# Mk3_v3_1415926535.net
KiCad netlist of a schematic drawn in EAGLE
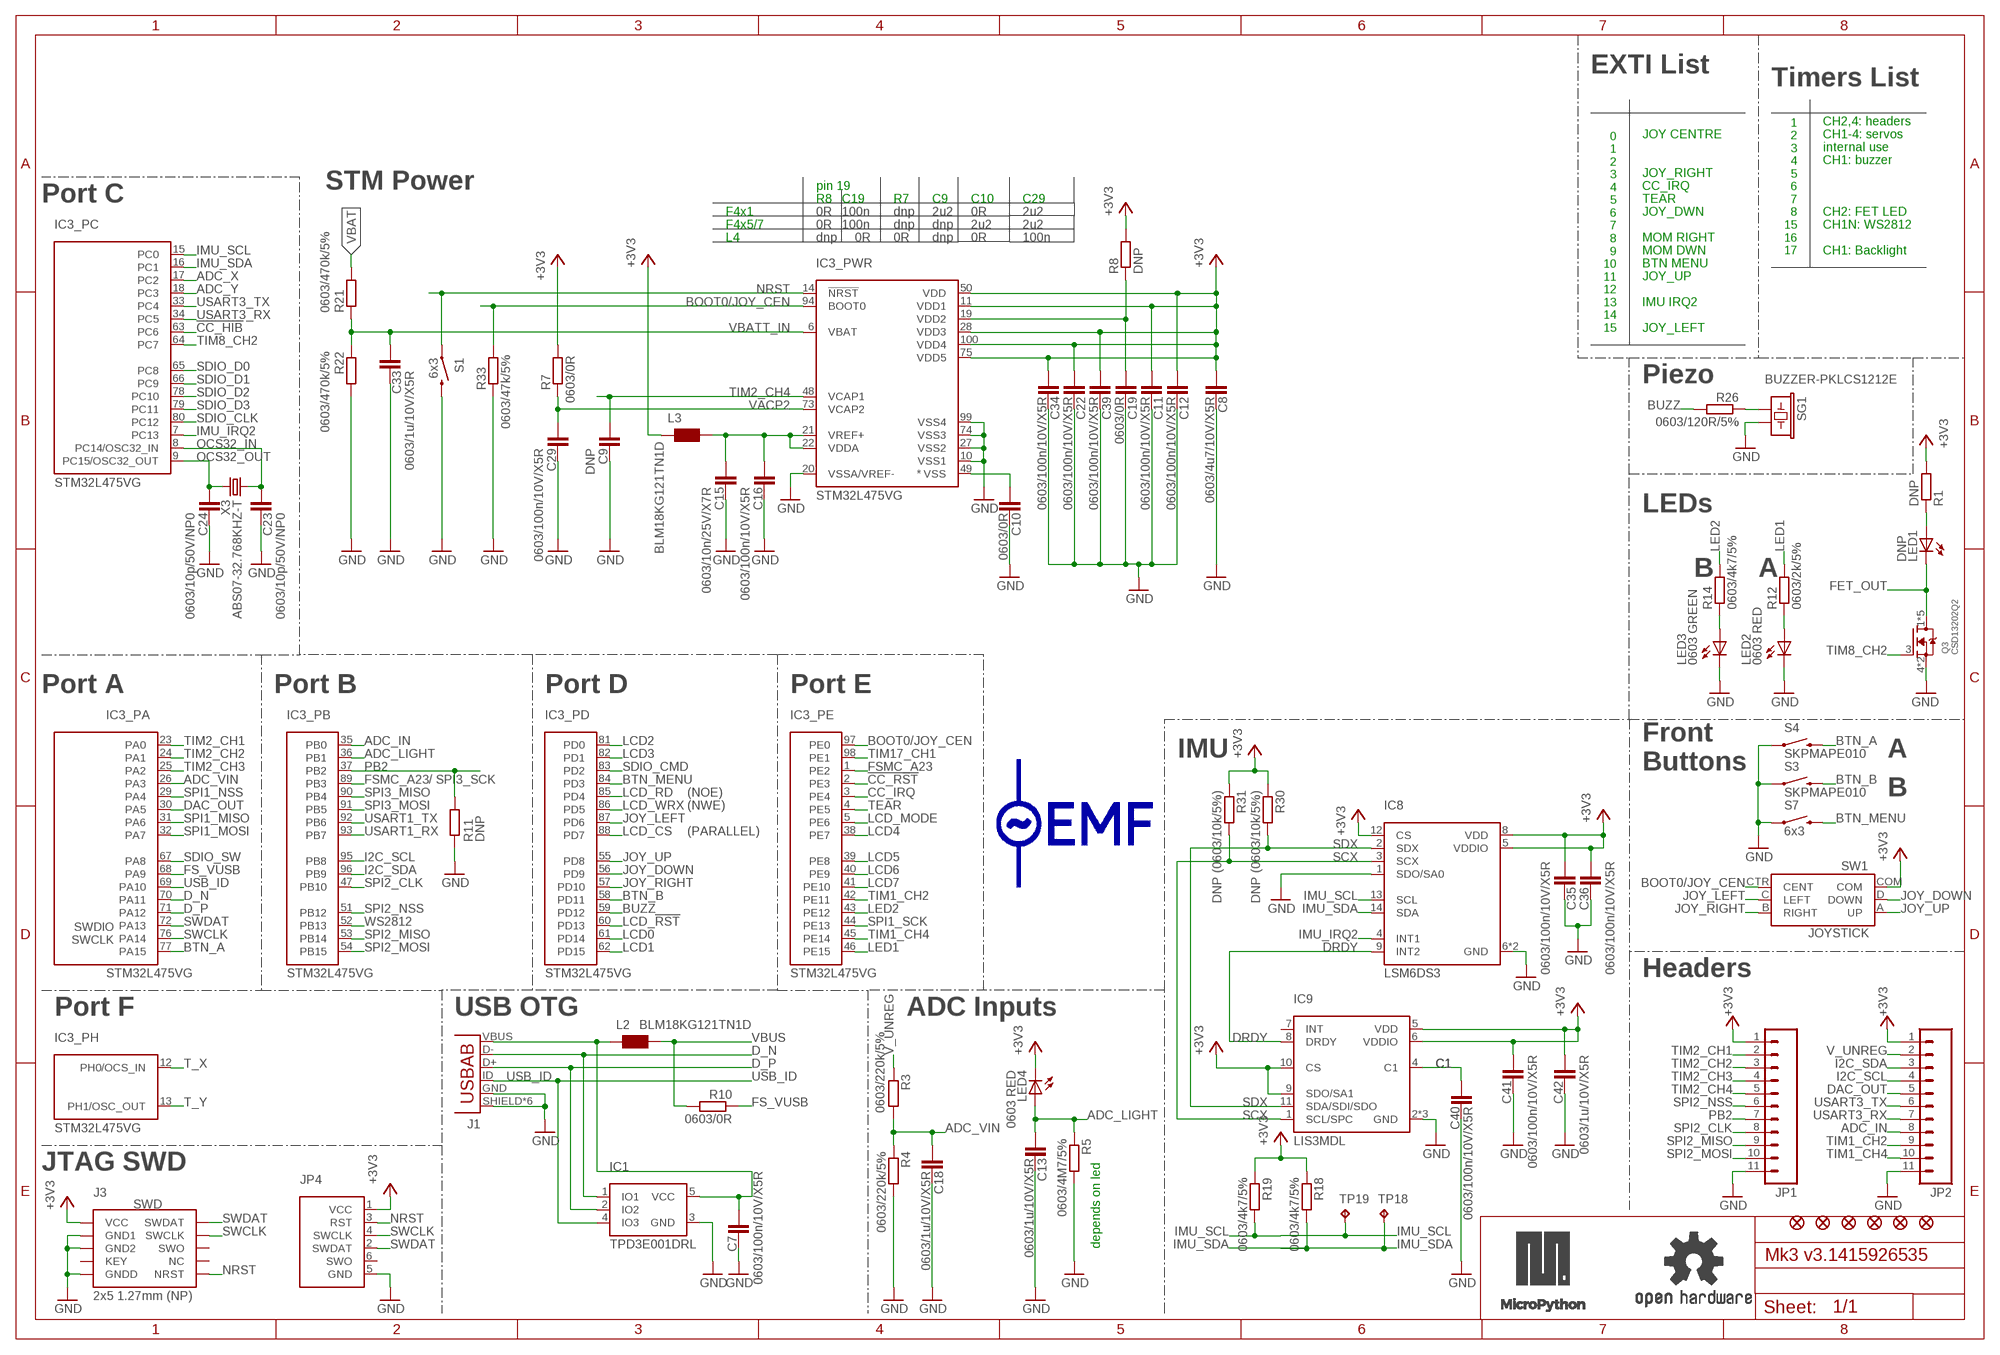
[diagram p0: schematic, sheet 1, part 1 of 2]
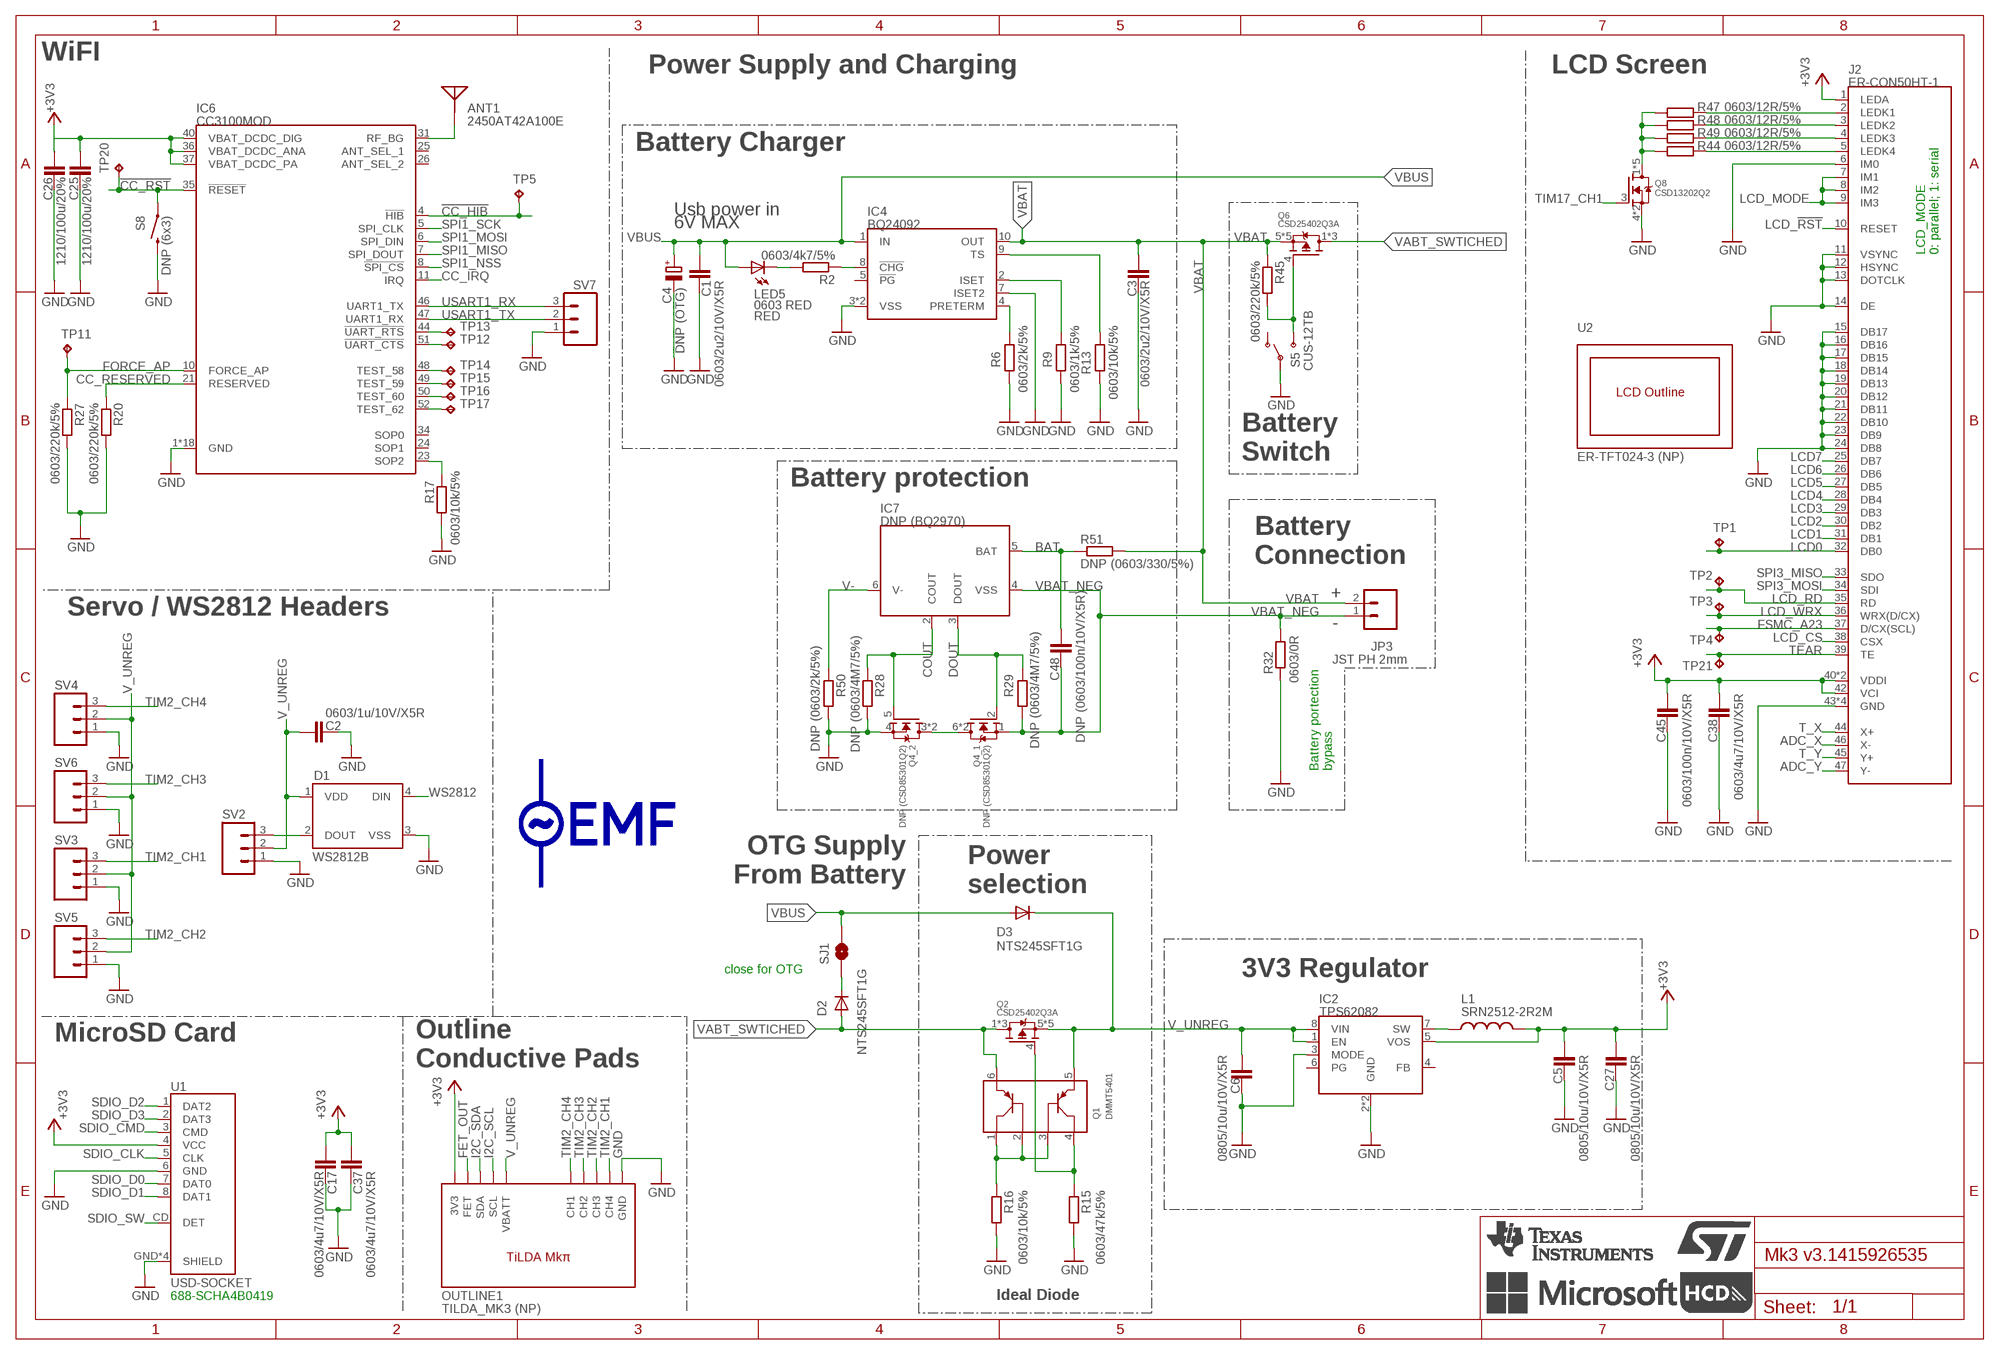
[diagram p1: schematic, sheet 1, part 2 of 2]

(export (version "E")
  (design (tool "Eeschema 10.0.6"))
  (components
    (comp (ref "ANT1")
      (value "2450AT42A100E")
      (footprint "eagle-import:2450AT42A100")
      (libsource (lib "eagle-import") (part "CHIPANT"))
    )
    (comp (ref "C1")
      (value "0603/2u2/10V/X5R")
      (footprint "eagle-import:C0603K-SMALL")
      (libsource (lib "eagle-import") (part "C-EUC0603K-SMALL"))
    )
    (comp (ref "C2")
      (value "0603/1u/10V/X5R")
      (footprint "eagle-import:C0603K-SMALL")
      (libsource (lib "eagle-import") (part "C-EUC0603K-SMALL"))
    )
    (comp (ref "C3")
      (value "0603/2u2/10V/X5R")
      (footprint "eagle-import:C0603K-SMALL")
      (libsource (lib "eagle-import") (part "C-EUC0603K-SMALL"))
    )
    (comp (ref "C4")
      (value "DNP (OTG)")
      (footprint "eagle-import:E2,5-6")
      (libsource (lib "eagle-import") (part "CPOL-EUE2.5-6"))
    )
    (comp (ref "C5")
      (value "0805/10u/10V/X5R")
      (footprint "eagle-import:C0805-N")
      (libsource (lib "eagle-import") (part "C-EUC0805-N"))
    )
    (comp (ref "C6")
      (value "0805/10u/10V/X5R")
      (footprint "eagle-import:C0805-N")
      (libsource (lib "eagle-import") (part "C-EUC0805-N"))
    )
    (comp (ref "C7")
      (value "0603/100n/10V/X5R")
      (footprint "eagle-import:C0603K-SMALL")
      (libsource (lib "eagle-import") (part "C-EUC0603K-SMALL"))
    )
    (comp (ref "C8")
      (value "0603/4u7/10V/X5R")
      (footprint "eagle-import:C0603K-SMALL")
      (libsource (lib "eagle-import") (part "C-EUC0603K-SMALL"))
    )
    (comp (ref "C9")
      (value "DNP")
      (footprint "eagle-import:C0603K-SMALL")
      (libsource (lib "eagle-import") (part "C-EUC0603K-SMALL"))
    )
    (comp (ref "C10")
      (value "0603/0R")
      (footprint "eagle-import:C0603K-SMALL")
      (libsource (lib "eagle-import") (part "C-EUC0603K-SMALL"))
    )
    (comp (ref "C11")
      (value "0603/100n/10V/X5R")
      (footprint "eagle-import:C0603K-SMALL")
      (libsource (lib "eagle-import") (part "C-EUC0603K-SMALL"))
    )
    (comp (ref "C12")
      (value "0603/100n/10V/X5R")
      (footprint "eagle-import:C0603K-SMALL")
      (libsource (lib "eagle-import") (part "C-EUC0603K-SMALL"))
    )
    (comp (ref "C13")
      (value "0603/1u/10V/X5R")
      (footprint "eagle-import:C0603K-SMALL")
      (libsource (lib "eagle-import") (part "C-EUC0603K-SMALL"))
    )
    (comp (ref "C15")
      (value "0603/10n/25V/X7R")
      (footprint "eagle-import:C0603K-SMALL")
      (libsource (lib "eagle-import") (part "C-EUC0603K-SMALL"))
    )
    (comp (ref "C16")
      (value "0603/100n/10V/X5R")
      (footprint "eagle-import:C0603K-SMALL")
      (libsource (lib "eagle-import") (part "C-EUC0603K-SMALL"))
    )
    (comp (ref "C17")
      (value "0603/4u7/10V/X5R")
      (footprint "eagle-import:C0603K-SMALL")
      (libsource (lib "eagle-import") (part "C-EUC0603K-SMALL"))
    )
    (comp (ref "C18")
      (value "0603/1u/10V/X5R")
      (footprint "eagle-import:C0603K-SMALL")
      (libsource (lib "eagle-import") (part "C-EUC0603K-SMALL"))
    )
    (comp (ref "C19")
      (value "0603/0R")
      (footprint "eagle-import:C0603K-SMALL")
      (libsource (lib "eagle-import") (part "C-EUC0603K-SMALL"))
    )
    (comp (ref "C22")
      (value "0603/100n/10V/X5R")
      (footprint "eagle-import:C0603K-SMALL")
      (libsource (lib "eagle-import") (part "C-EUC0603K-SMALL"))
    )
    (comp (ref "C23")
      (value "0603/10p/50V/NP0")
      (footprint "eagle-import:C0603K-SMALL")
      (libsource (lib "eagle-import") (part "C-EUC0603K-SMALL"))
    )
    (comp (ref "C24")
      (value "0603/10p/50V/NP0")
      (footprint "eagle-import:C0603K-SMALL")
      (libsource (lib "eagle-import") (part "C-EUC0603K-SMALL"))
    )
    (comp (ref "C25")
      (value "1210/100u/20%")
      (footprint "eagle-import:C1210K")
      (libsource (lib "eagle-import") (part "C-EUC1210K"))
    )
    (comp (ref "C26")
      (value "1210/100u/20%")
      (footprint "eagle-import:C1210K")
      (libsource (lib "eagle-import") (part "C-EUC1210K"))
    )
    (comp (ref "C27")
      (value "0805/10u/10V/X5R")
      (footprint "eagle-import:C0805-N")
      (libsource (lib "eagle-import") (part "C-EUC0805-N"))
    )
    (comp (ref "C29")
      (value "0603/100n/10V/X5R")
      (footprint "eagle-import:C0603K-SMALL")
      (libsource (lib "eagle-import") (part "C-EUC0603K-SMALL"))
    )
    (comp (ref "C33")
      (value "0603/1u/10V/X5R")
      (footprint "eagle-import:C0603K-SMALL")
      (libsource (lib "eagle-import") (part "C-EUC0603K-SMALL"))
    )
    (comp (ref "C34")
      (value "0603/100n/10V/X5R")
      (footprint "eagle-import:C0603K-SMALL")
      (libsource (lib "eagle-import") (part "C-EUC0603K-SMALL"))
    )
    (comp (ref "C35")
      (value "0603/100n/10V/X5R")
      (footprint "eagle-import:C0603K-SMALL")
      (libsource (lib "eagle-import") (part "C-EUC0603K-SMALL"))
    )
    (comp (ref "C36")
      (value "0603/100n/10V/X5R")
      (footprint "eagle-import:C0603K-SMALL")
      (libsource (lib "eagle-import") (part "C-EUC0603K-SMALL"))
    )
    (comp (ref "C37")
      (value "0603/4u7/10V/X5R")
      (footprint "eagle-import:C0603K-SMALL")
      (libsource (lib "eagle-import") (part "C-EUC0603K-SMALL"))
    )
    (comp (ref "C38")
      (value "0603/4u7/10V/X5R")
      (footprint "eagle-import:C0603K-SMALL")
      (libsource (lib "eagle-import") (part "C-EUC0603K-SMALL"))
    )
    (comp (ref "C39")
      (value "0603/100n/10V/X5R")
      (footprint "eagle-import:C0603K-SMALL")
      (libsource (lib "eagle-import") (part "C-EUC0603K-SMALL"))
    )
    (comp (ref "C40")
      (value "0603/100n/10V/X5R")
      (footprint "eagle-import:C0603K-SMALL")
      (libsource (lib "eagle-import") (part "C-EUC0603K-SMALL"))
    )
    (comp (ref "C41")
      (value "0603/100n/10V/X5R")
      (footprint "eagle-import:C0603K-SMALL")
      (libsource (lib "eagle-import") (part "C-EUC0603K-SMALL"))
    )
    (comp (ref "C42")
      (value "0603/1u/10V/X5R")
      (footprint "eagle-import:C0603K-SMALL")
      (libsource (lib "eagle-import") (part "C-EUC0603K-SMALL"))
    )
    (comp (ref "C45")
      (value "0603/100n/10V/X5R")
      (footprint "eagle-import:C0603K-SMALL")
      (libsource (lib "eagle-import") (part "C-EUC0603K-SMALL"))
    )
    (comp (ref "C48")
      (value "DNP (0603/100n/10V/X5R)")
      (footprint "eagle-import:C0603K-SMALL")
      (libsource (lib "eagle-import") (part "C-EUC0603K-SMALL"))
    )
    (comp (ref "D1")
      (value "WS2812B")
      (footprint "eagle-import:WS2812B")
      (libsource (lib "eagle-import") (part "WS2812B"))
    )
    (comp (ref "D2")
      (value "NTS245SFT1G")
      (footprint "eagle-import:SOD123")
      (libsource (lib "eagle-import") (part "1N4148-SOD123"))
    )
    (comp (ref "D3")
      (value "NTS245SFT1G")
      (footprint "eagle-import:SOD123")
      (libsource (lib "eagle-import") (part "1N4148-SOD123"))
    )
    (comp (ref "FID1")
      (value "FIDUCIAL1X2.5-STOP")
      (footprint "eagle-import:FIDUCIAL-1X2.5-STOP")
      (libsource (lib "eagle-import") (part "FIDUCIAL1X2.5-STOP"))
    )
    (comp (ref "FID2")
      (value "FIDUCIAL1X2.5-STOP")
      (footprint "eagle-import:FIDUCIAL-1X2.5-STOP")
      (libsource (lib "eagle-import") (part "FIDUCIAL1X2.5-STOP"))
    )
    (comp (ref "FID3")
      (value "FIDUCIAL1X2.5-STOP")
      (footprint "eagle-import:FIDUCIAL-1X2.5-STOP")
      (libsource (lib "eagle-import") (part "FIDUCIAL1X2.5-STOP"))
    )
    (comp (ref "FID4")
      (value "FIDUCIAL1X2.5-STOP")
      (footprint "eagle-import:FIDUCIAL-1X2.5-STOP")
      (libsource (lib "eagle-import") (part "FIDUCIAL1X2.5-STOP"))
    )
    (comp (ref "FID5")
      (value "FIDUCIAL1X2.5-STOP")
      (footprint "eagle-import:FIDUCIAL-1X2.5-STOP")
      (libsource (lib "eagle-import") (part "FIDUCIAL1X2.5-STOP"))
    )
    (comp (ref "FID6")
      (value "FIDUCIAL1X2.5-STOP")
      (footprint "eagle-import:FIDUCIAL-1X2.5-STOP")
      (libsource (lib "eagle-import") (part "FIDUCIAL1X2.5-STOP"))
    )
    (comp (ref "IC1")
      (value "TPD3E001DRL")
      (footprint "eagle-import:DRL-5")
      (libsource (lib "eagle-import") (part "TPD3E001DRL"))
    )
    (comp (ref "IC2")
      (value "TPS62082")
      (footprint "eagle-import:WSON8")
      (libsource (lib "eagle-import") (part "TPS62082"))
    )
    (comp (ref "IC3")
      (value "STM32L475VG")
      (footprint "eagle-import:TQFP100")
      (fields (field (name "FARNELL") "2432116"))
      (libsource (lib "eagle-import") (part "STM32F401V"))
    )
    (comp (ref "IC4")
      (value "BQ24092")
      (footprint "eagle-import:HVSSOP10")
      (libsource (lib "eagle-import") (part "BQ2409X"))
    )
    (comp (ref "IC6")
      (value "CC3100MOD")
      (footprint "eagle-import:CC3100MOD-LWK")
      (libsource (lib "eagle-import") (part "CC3100MOD-LWK"))
    )
    (comp (ref "IC7")
      (value "DNP (BQ2970)")
      (footprint "eagle-import:WSON-6")
      (libsource (lib "eagle-import") (part "BQ2970"))
    )
    (comp (ref "IC8")
      (value "LSM6DS3")
      (footprint "eagle-import:LGA14")
      (libsource (lib "eagle-import") (part "LSM6DS3"))
    )
    (comp (ref "IC9")
      (value "LIS3MDL")
      (footprint "eagle-import:LGA12")
      (libsource (lib "eagle-import") (part "LIS3MDL"))
    )
    (comp (ref "J1")
      (value "ZX62-AB-5PA(11)")
      (footprint "eagle-import:USB-AB-MICRO-SMD_LWK")
      (libsource (lib "eagle-import") (part "USB-AB-LWK"))
    )
    (comp (ref "J2")
      (value "ER-CON50HT-1")
      (footprint "eagle-import:FH12-50S-0.5SH")
      (libsource (lib "eagle-import") (part "ER-TFT024-3"))
    )
    (comp (ref "J3")
      (value "2x5 1.27mm (NP)")
      (footprint "eagle-import:PINHEAD_2X05_127")
      (libsource (lib "eagle-import") (part "SWD_SHROUD-PINHEAD"))
    )
    (comp (ref "JP1")
      (value "(NP)")
      (footprint "eagle-import:1X11")
      (libsource (lib "eagle-import") (part "M11PTH"))
    )
    (comp (ref "JP2")
      (value "(NP)")
      (footprint "eagle-import:1X11")
      (libsource (lib "eagle-import") (part "M11PTH"))
    )
    (comp (ref "JP3")
      (value "JST PH 2mm")
      (footprint "eagle-import:JST-2-SMD")
      (libsource (lib "eagle-import") (part "M02-JST-2MM-SMT"))
    )
    (comp (ref "JP4")
      (value "(NP)")
      (footprint "eagle-import:TC2030-MCP-NL")
      (libsource (lib "eagle-import") (part "TC2030-SWDNL"))
    )
    (comp (ref "L1")
      (value "SRN2512-2R2M")
      (footprint "eagle-import:1008")
      (libsource (lib "eagle-import") (part "INDUCTOR1008"))
    )
    (comp (ref "L2")
      (value "BLM18KG121TN1D")
      (footprint "eagle-import:WUERTH-0805")
      (libsource (lib "eagle-import") (part "WE-CBF_0805"))
    )
    (comp (ref "L3")
      (value "BLM18KG121TN1D")
      (footprint "eagle-import:WUERTH-0805")
      (libsource (lib "eagle-import") (part "WE-CBF_0805"))
    )
    (comp (ref "LED1")
      (value "DNP")
      (footprint "eagle-import:LED5MM")
      (libsource (lib "eagle-import") (part "LED5MM"))
    )
    (comp (ref "LED2")
      (value "0603 RED")
      (footprint "eagle-import:LED-0603-CORRECT")
      (fields (field (name "COLOUR") "RED"))
      (libsource (lib "eagle-import") (part "LED0603-CORRECT"))
    )
    (comp (ref "LED3")
      (value "0603 GREEN")
      (footprint "eagle-import:LED-0603-CORRECT")
      (fields (field (name "COLOUR") "GREEN"))
      (libsource (lib "eagle-import") (part "LED0603-CORRECT"))
    )
    (comp (ref "LED4")
      (value "0603 RED")
      (footprint "eagle-import:LED-0603-CORRECT")
      (libsource (lib "eagle-import") (part "LED0603-CORRECT"))
    )
    (comp (ref "LED5")
      (value "0603 RED")
      (footprint "eagle-import:LED-0603-CORRECT")
      (fields (field (name "COLOUR") "RED"))
      (libsource (lib "eagle-import") (part "LED0603-CORRECT"))
    )
    (comp (ref "LOGO1")
      (value "OSHW-LOGOM (NP)")
      (footprint "eagle-import:OSHW-LOGO-M")
      (libsource (lib "eagle-import") (part "OSHW-LOGOM"))
    )
    (comp (ref "LOGO2")
      (value "LOGO_TI-4MM (NP)")
      (footprint "eagle-import:LOGO_TI_4MM")
      (libsource (lib "eagle-import") (part "LOGO_TI-4MM"))
    )
    (comp (ref "LOGO3")
      (value "LOGO_ST-4MM (NP)")
      (footprint "eagle-import:LOGO_ST_4MM")
      (libsource (lib "eagle-import") (part "LOGO_ST-4MM"))
    )
    (comp (ref "LOGO4")
      (value "LOGO_HCD-4MM (NP)")
      (footprint "eagle-import:LOGO_HDC_4MM")
      (libsource (lib "eagle-import") (part "LOGO_HCD-4MM"))
    )
    (comp (ref "LOGO5")
      (value "LOGO_MICROSOFT-4MM (NP)")
      (footprint "eagle-import:LOGO_MS_4MM")
      (libsource (lib "eagle-import") (part "LOGO_MICROSOFT-4MM"))
    )
    (comp (ref "LOGO6")
      (value "LOGO_MICROPYTHON-8MM (NP)")
      (footprint "eagle-import:LOGO_MICROPYTHON_8MM")
      (libsource (lib "eagle-import") (part "LOGO_MICROPYTHON-8MM"))
    )
    (comp (ref "OUTLINE1")
      (value "TILDA_MK3 (NP)")
      (footprint "eagle-import:TILDA_MKE_OUTLINE")
      (libsource (lib "eagle-import") (part "TILDA_MK3_BOARDOUTLINE"))
    )
    (comp (ref "Q1")
      (value "DMMT5401")
      (footprint "eagle-import:SOT26")
      (libsource (lib "eagle-import") (part "DMMT5401"))
    )
    (comp (ref "Q2")
      (value "CSD25402Q3A")
      (footprint "eagle-import:Q3A")
      (libsource (lib "eagle-import") (part "CSD25402Q3A"))
    )
    (comp (ref "Q3")
      (value "CSD13202Q2")
      (footprint "eagle-import:Q2")
      (libsource (lib "eagle-import") (part "CSD13202Q2"))
    )
    (comp (ref "Q4")
      (value "DNP (CSD85301Q2)")
      (footprint "eagle-import:Q2_DUAL")
      (fields (field (name "FARNELL") "2470183"))
      (libsource (lib "eagle-import") (part "CSD85301Q2"))
    )
    (comp (ref "Q6")
      (value "CSD25402Q3A")
      (footprint "eagle-import:Q3A")
      (libsource (lib "eagle-import") (part "CSD25402Q3A"))
    )
    (comp (ref "Q8")
      (value "CSD13202Q2")
      (footprint "eagle-import:Q2")
      (libsource (lib "eagle-import") (part "CSD13202Q2"))
    )
    (comp (ref "R1")
      (value "DNP")
      (footprint "eagle-import:0207_10")
      (libsource (lib "eagle-import") (part "R-EU_0207/10"))
    )
    (comp (ref "R2")
      (value "0603/4k7/5%")
      (footprint "eagle-import:C0603K-SMALL")
      (libsource (lib "eagle-import") (part "R-EU_0603K-SMALL"))
    )
    (comp (ref "R3")
      (value "0603/220k/5%")
      (footprint "eagle-import:C0603K-SMALL")
      (libsource (lib "eagle-import") (part "R-EU_0603K-SMALL"))
    )
    (comp (ref "R4")
      (value "0603/220k/5%")
      (footprint "eagle-import:C0603K-SMALL")
      (libsource (lib "eagle-import") (part "R-EU_0603K-SMALL"))
    )
    (comp (ref "R5")
      (value "0603/4M7/5%")
      (footprint "eagle-import:C0603K-SMALL")
      (libsource (lib "eagle-import") (part "R-EU_0603K-SMALL"))
    )
    (comp (ref "R6")
      (value "0603/2k/5%")
      (footprint "eagle-import:C0603K-SMALL")
      (libsource (lib "eagle-import") (part "R-EU_0603K-SMALL"))
    )
    (comp (ref "R7")
      (value "0603/0R")
      (footprint "eagle-import:C0603K-SMALL")
      (libsource (lib "eagle-import") (part "R-EU_0603K-SMALL"))
    )
    (comp (ref "R8")
      (value "DNP")
      (footprint "eagle-import:C0603K-SMALL")
      (libsource (lib "eagle-import") (part "R-EU_0603K-SMALL"))
    )
    (comp (ref "R9")
      (value "0603/1k/5%")
      (footprint "eagle-import:C0603K-SMALL")
      (libsource (lib "eagle-import") (part "R-EU_0603K-SMALL"))
    )
    (comp (ref "R10")
      (value "0603/0R")
      (footprint "eagle-import:C0603K-SMALL")
      (libsource (lib "eagle-import") (part "R-EU_0603K-SMALL"))
    )
    (comp (ref "R11")
      (value "DNP")
      (footprint "eagle-import:C0603K-SMALL")
      (libsource (lib "eagle-import") (part "R-EU_0603K-SMALL"))
    )
    (comp (ref "R12")
      (value "0603/2k/5%")
      (footprint "eagle-import:C0603K-SMALL")
      (libsource (lib "eagle-import") (part "R-EU_0603K-SMALL"))
    )
    (comp (ref "R13")
      (value "0603/10k/5%")
      (footprint "eagle-import:C0603K-SMALL")
      (libsource (lib "eagle-import") (part "R-EU_0603K-SMALL"))
    )
    (comp (ref "R14")
      (value "0603/4k7/5%")
      (footprint "eagle-import:C0603K-SMALL")
      (libsource (lib "eagle-import") (part "R-EU_0603K-SMALL"))
    )
    (comp (ref "R15")
      (value "0603/47k/5%")
      (footprint "eagle-import:C0603K-SMALL")
      (libsource (lib "eagle-import") (part "R-EU_0603K-SMALL"))
    )
    (comp (ref "R16")
      (value "0603/10k/5%")
      (footprint "eagle-import:C0603K-SMALL")
      (libsource (lib "eagle-import") (part "R-EU_0603K-SMALL"))
    )
    (comp (ref "R17")
      (value "0603/10k/5%")
      (footprint "eagle-import:C0603K-SMALL")
      (libsource (lib "eagle-import") (part "R-EU_0603K-SMALL"))
    )
    (comp (ref "R18")
      (value "0603/4k7/5%")
      (footprint "eagle-import:C0603K-SMALL")
      (libsource (lib "eagle-import") (part "R-EU_0603K-SMALL"))
    )
    (comp (ref "R19")
      (value "0603/4k7/5%")
      (footprint "eagle-import:C0603K-SMALL")
      (libsource (lib "eagle-import") (part "R-EU_0603K-SMALL"))
    )
    (comp (ref "R20")
      (value "0603/220k/5%")
      (footprint "eagle-import:C0603K-SMALL")
      (libsource (lib "eagle-import") (part "R-EU_0603K-SMALL"))
    )
    (comp (ref "R21")
      (value "0603/470k/5%")
      (footprint "eagle-import:C0603K-SMALL")
      (libsource (lib "eagle-import") (part "R-EU_0603K-SMALL"))
    )
    (comp (ref "R22")
      (value "0603/470k/5%")
      (footprint "eagle-import:C0603K-SMALL")
      (libsource (lib "eagle-import") (part "R-EU_0603K-SMALL"))
    )
    (comp (ref "R26")
      (value "0603/120R/5%")
      (footprint "eagle-import:C0603K-SMALL")
      (libsource (lib "eagle-import") (part "R-EU_0603K-SMALL"))
    )
    (comp (ref "R27")
      (value "0603/220k/5%")
      (footprint "eagle-import:C0603K-SMALL")
      (libsource (lib "eagle-import") (part "R-EU_0603K-SMALL"))
    )
    (comp (ref "R28")
      (value "DNP (0603/4M7/5%)")
      (footprint "eagle-import:C0603K-SMALL")
      (libsource (lib "eagle-import") (part "R-EU_0603K-SMALL"))
    )
    (comp (ref "R29")
      (value "DNP (0603/4M7/5%)")
      (footprint "eagle-import:C0603K-SMALL")
      (libsource (lib "eagle-import") (part "R-EU_0603K-SMALL"))
    )
    (comp (ref "R30")
      (value "DNP (0603/10k/5%)")
      (footprint "eagle-import:C0603K-SMALL")
      (libsource (lib "eagle-import") (part "R-EU_0603K-SMALL"))
    )
    (comp (ref "R31")
      (value "DNP (0603/10k/5%)")
      (footprint "eagle-import:C0603K-SMALL")
      (libsource (lib "eagle-import") (part "R-EU_0603K-SMALL"))
    )
    (comp (ref "R32")
      (value "0603/0R")
      (footprint "eagle-import:C0603K-SMALL")
      (libsource (lib "eagle-import") (part "R-EU_0603K-SMALL"))
    )
    (comp (ref "R33")
      (value "0603/47k/5%")
      (footprint "eagle-import:C0603K-SMALL")
      (libsource (lib "eagle-import") (part "R-EU_0603K-SMALL"))
    )
    (comp (ref "R44")
      (value "0603/12R/5%")
      (footprint "eagle-import:C0603K-SMALL")
      (libsource (lib "eagle-import") (part "R-EU_0603K-SMALL"))
    )
    (comp (ref "R45")
      (value "0603/220k/5%")
      (footprint "eagle-import:C0603K-SMALL")
      (libsource (lib "eagle-import") (part "R-EU_0603K-SMALL"))
    )
    (comp (ref "R47")
      (value "0603/12R/5%")
      (footprint "eagle-import:C0603K-SMALL")
      (libsource (lib "eagle-import") (part "R-EU_0603K-SMALL"))
    )
    (comp (ref "R48")
      (value "0603/12R/5%")
      (footprint "eagle-import:C0603K-SMALL")
      (libsource (lib "eagle-import") (part "R-EU_0603K-SMALL"))
    )
    (comp (ref "R49")
      (value "0603/12R/5%")
      (footprint "eagle-import:C0603K-SMALL")
      (libsource (lib "eagle-import") (part "R-EU_0603K-SMALL"))
    )
    (comp (ref "R50")
      (value "DNP (0603/2k/5%)")
      (footprint "eagle-import:C0603K-SMALL")
      (libsource (lib "eagle-import") (part "R-EU_0603K-SMALL"))
    )
    (comp (ref "R51")
      (value "DNP (0603/330/5%)")
      (footprint "eagle-import:C0603K-SMALL")
      (libsource (lib "eagle-import") (part "R-EU_0603K-SMALL"))
    )
    (comp (ref "S1")
      (value "6x3")
      (footprint "eagle-import:TACTILE-SWITCH-1101NE")
      (libsource (lib "eagle-import") (part "SWITCH-MOMENTARY-2-SMD-1101NE"))
    )
    (comp (ref "S3")
      (value "SKPMAPE010")
      (footprint "eagle-import:SKPMAPE010-COMBINED")
      (libsource (lib "eagle-import") (part "SWITCH-MOMENTARY-2-SKPMAPE010-COMBINED"))
    )
    (comp (ref "S4")
      (value "SKPMAPE010")
      (footprint "eagle-import:SKPMAPE010-COMBINED")
      (libsource (lib "eagle-import") (part "SWITCH-MOMENTARY-2-SKPMAPE010-COMBINED"))
    )
    (comp (ref "S5")
      (value "CUS-12TB")
      (footprint "eagle-import:SWITCH-SPST-SMD-A")
      (libsource (lib "eagle-import") (part "SWITCH-SPST-SMD-A"))
    )
    (comp (ref "S7")
      (value "6x3")
      (footprint "eagle-import:TACTILE-SWITCH-1101NE")
      (libsource (lib "eagle-import") (part "SWITCH-MOMENTARY-2-SMD-1101NE"))
    )
    (comp (ref "S8")
      (value "DNP (6x3)")
      (footprint "eagle-import:TACTILE-SWITCH-1101NE")
      (libsource (lib "eagle-import") (part "SWITCH-MOMENTARY-2-SMD-1101NE"))
    )
    (comp (ref "SG1")
      (value "BUZZER-PKLCS1212E")
      (footprint "eagle-import:BUZZER-PKLCS1212E")
      (libsource (lib "eagle-import") (part "BUZZER-PKLCS1212E"))
    )
    (comp (ref "SJ1")
      (value "OTG (NP)")
      (footprint "eagle-import:SJ_2S-NO")
      (libsource (lib "eagle-import") (part "SOLDERJUMPERNO"))
    )
    (comp (ref "SV2")
      (value "(NP)")
      (footprint "eagle-import:1X03")
      (libsource (lib "eagle-import") (part "M03PTH"))
    )
    (comp (ref "SV3")
      (value "(NP)")
      (footprint "eagle-import:1X03")
      (libsource (lib "eagle-import") (part "M03PTH"))
    )
    (comp (ref "SV4")
      (value "(NP)")
      (footprint "eagle-import:1X03")
      (libsource (lib "eagle-import") (part "M03PTH"))
    )
    (comp (ref "SV5")
      (value "(NP)")
      (footprint "eagle-import:1X03")
      (libsource (lib "eagle-import") (part "M03PTH"))
    )
    (comp (ref "SV6")
      (value "(NP)")
      (footprint "eagle-import:1X03")
      (libsource (lib "eagle-import") (part "M03PTH"))
    )
    (comp (ref "SV7")
      (value "(NP)")
      (footprint "eagle-import:1X03")
      (libsource (lib "eagle-import") (part "M03PTH"))
    )
    (comp (ref "SW1")
      (value "JOYSTICK")
      (footprint "eagle-import:JOYSTICK_MULTICOMP_NOSILK")
      (libsource (lib "eagle-import") (part "JOYSTICK_MINI_MULTICOM_NOSILK"))
    )
    (comp (ref "TP1")
      (value "(NP)")
      (footprint "eagle-import:B1,27")
      (libsource (lib "eagle-import") (part "TPB1,27"))
    )
    (comp (ref "TP2")
      (value "(NP)")
      (footprint "eagle-import:B1,27")
      (libsource (lib "eagle-import") (part "TPB1,27"))
    )
    (comp (ref "TP3")
      (value "(NP)")
      (footprint "eagle-import:B1,27")
      (libsource (lib "eagle-import") (part "TPB1,27"))
    )
    (comp (ref "TP4")
      (value "(NP)")
      (footprint "eagle-import:B1,27")
      (libsource (lib "eagle-import") (part "TPB1,27"))
    )
    (comp (ref "TP5")
      (value "(NP)")
      (footprint "eagle-import:B1,27")
      (libsource (lib "eagle-import") (part "TPB1,27"))
    )
    (comp (ref "TP11")
      (value "(NP)")
      (footprint "eagle-import:B1,27")
      (libsource (lib "eagle-import") (part "TPB1,27"))
    )
    (comp (ref "TP12")
      (value "(NP)")
      (footprint "eagle-import:B1,27")
      (libsource (lib "eagle-import") (part "TPB1,27"))
    )
    (comp (ref "TP13")
      (value "(NP)")
      (footprint "eagle-import:B1,27")
      (libsource (lib "eagle-import") (part "TPB1,27"))
    )
    (comp (ref "TP14")
      (value "(NP)")
      (footprint "eagle-import:B1,27")
      (libsource (lib "eagle-import") (part "TPB1,27"))
    )
    (comp (ref "TP15")
      (value "(NP)")
      (footprint "eagle-import:B1,27")
      (libsource (lib "eagle-import") (part "TPB1,27"))
    )
    (comp (ref "TP16")
      (value "(NP)")
      (footprint "eagle-import:B1,27")
      (libsource (lib "eagle-import") (part "TPB1,27"))
    )
    (comp (ref "TP17")
      (value "(NP)")
      (footprint "eagle-import:B1,27")
      (libsource (lib "eagle-import") (part "TPB1,27"))
    )
    (comp (ref "TP18")
      (value "(NP)")
      (footprint "eagle-import:B1,27")
      (libsource (lib "eagle-import") (part "TPB1,27"))
    )
    (comp (ref "TP19")
      (value "(NP)")
      (footprint "eagle-import:B1,27")
      (libsource (lib "eagle-import") (part "TPB1,27"))
    )
    (comp (ref "TP20")
      (value "(NP)")
      (footprint "eagle-import:B1,27")
      (libsource (lib "eagle-import") (part "TPB1,27"))
    )
    (comp (ref "TP21")
      (value "(NP)")
      (footprint "eagle-import:B1,27")
      (libsource (lib "eagle-import") (part "TPB1,27"))
    )
    (comp (ref "U1")
      (value "USD-SOCKET")
      (footprint "eagle-import:0011XAAX09X")
      (libsource (lib "eagle-import") (part "USD-SOCKET-SDIO"))
    )
    (comp (ref "U2")
      (value "ER-TFT024-3 (NP)")
      (footprint "eagle-import:ER-TFT024-3")
      (libsource (lib "eagle-import") (part "ER-TFT024-3-OUTLINE"))
    )
    (comp (ref "X3")
      (value "ABS07-32.768KHZ-T")
      (footprint "eagle-import:RESONATOR_EPSON_FC_145")
      (libsource (lib "eagle-import") (part "RESONATOR_EPSON_FC_145"))
    )
  )
  (nets
    (net (code "1") (name "+3V3") (class "Default")
      (node (ref "C11") (pin "2") (pinfunction "2_2") (pintype "passive"))
      (node (ref "C12") (pin "2") (pinfunction "2_2") (pintype "passive"))
      (node (ref "C17") (pin "2") (pinfunction "2_2") (pintype "passive"))
      (node (ref "C22") (pin "2") (pinfunction "2_2") (pintype "passive"))
      (node (ref "C25") (pin "1") (pinfunction "1_1") (pintype "passive"))
      (node (ref "C26") (pin "1") (pinfunction "1_1") (pintype "passive"))
      (node (ref "C27") (pin "1") (pinfunction "1_1") (pintype "passive"))
      (node (ref "C34") (pin "2") (pinfunction "2_2") (pintype "passive"))
      (node (ref "C35") (pin "1") (pinfunction "1_1") (pintype "passive"))
      (node (ref "C36") (pin "1") (pinfunction "1_1") (pintype "passive"))
      (node (ref "C37") (pin "2") (pinfunction "2_2") (pintype "passive"))
      (node (ref "C38") (pin "2") (pinfunction "2_2") (pintype "passive"))
      (node (ref "C39") (pin "2") (pinfunction "2_2") (pintype "passive"))
      (node (ref "C41") (pin "1") (pinfunction "1_1") (pintype "passive"))
      (node (ref "C42") (pin "1") (pinfunction "1_1") (pintype "passive"))
      (node (ref "C45") (pin "2") (pinfunction "2_2") (pintype "passive"))
      (node (ref "C5") (pin "1") (pinfunction "1_1") (pintype "passive"))
      (node (ref "C8") (pin "2") (pinfunction "2_2") (pintype "passive"))
      (node (ref "IC2") (pin "5") (pinfunction "VOS_5") (pintype "input"))
      (node (ref "IC3") (pin "100") (pinfunction "VDD4_100") (pintype "bidirectional"))
      (node (ref "IC3") (pin "11") (pinfunction "VDD1_11") (pintype "bidirectional"))
      (node (ref "IC3") (pin "28") (pinfunction "VDD3_28") (pintype "bidirectional"))
      (node (ref "IC3") (pin "50") (pinfunction "VDD_50") (pintype "bidirectional"))
      (node (ref "IC3") (pin "75") (pinfunction "VDD5_75") (pintype "bidirectional"))
      (node (ref "IC6") (pin "36") (pinfunction "VBAT_DCDC_ANA_36") (pintype "power_in"))
      (node (ref "IC6") (pin "37") (pinfunction "VBAT_DCDC_PA_37") (pintype "power_in"))
      (node (ref "IC6") (pin "40") (pinfunction "VBAT_DCDC_DIG_40") (pintype "power_in"))
      (node (ref "IC8") (pin "12") (pinfunction "CS_12") (pintype "input"))
      (node (ref "IC8") (pin "5") (pinfunction "VDDIO_5") (pintype "power_in"))
      (node (ref "IC8") (pin "8") (pinfunction "VDD_8") (pintype "power_in"))
      (node (ref "IC9") (pin "10") (pinfunction "CS_10") (pintype "input"))
      (node (ref "IC9") (pin "5") (pinfunction "VDD_5") (pintype "power_in"))
      (node (ref "IC9") (pin "6") (pinfunction "VDDIO_6") (pintype "power_in"))
      (node (ref "IC9") (pin "9") (pinfunction "SDO/SA1_9") (pintype "bidirectional"))
      (node (ref "J2") (pin "1") (pinfunction "LEDA_1") (pintype "passive"))
      (node (ref "J2") (pin "40") (pinfunction "VDDI_40") (pintype "power_in"))
      (node (ref "J2") (pin "41") (pinfunction "VDDI_41") (pintype "power_in"))
      (node (ref "J2") (pin "42") (pinfunction "VCI_42") (pintype "power_in"))
      (node (ref "J3") (pin "1") (pinfunction "VCC_1") (pintype "power_in"))
      (node (ref "JP1") (pin "1") (pinfunction "1_1") (pintype "passive"))
      (node (ref "JP2") (pin "1") (pinfunction "1_1") (pintype "passive"))
      (node (ref "JP4") (pin "1") (pinfunction "VCC_1") (pintype "power_in"))
      (node (ref "L1") (pin "2") (pinfunction "2_2") (pintype "passive"))
      (node (ref "L3") (pin "1") (pinfunction "1_1") (pintype "passive"))
      (node (ref "LED4") (pin "C") (pinfunction "C_C") (pintype "passive"))
      (node (ref "OUTLINE1") (pin "3V3") (pinfunction "3V3_3V3") (pintype "bidirectional"))
      (node (ref "R1") (pin "2") (pinfunction "2_2") (pintype "passive"))
      (node (ref "R18") (pin "1") (pinfunction "1_1") (pintype "passive"))
      (node (ref "R19") (pin "1") (pinfunction "1_1") (pintype "passive"))
      (node (ref "R30") (pin "1") (pinfunction "1_1") (pintype "passive"))
      (node (ref "R31") (pin "1") (pinfunction "1_1") (pintype "passive"))
      (node (ref "R7") (pin "1") (pinfunction "1_1") (pintype "passive"))
      (node (ref "R8") (pin "2") (pinfunction "2_2") (pintype "passive"))
      (node (ref "SW1") (pin "COM") (pinfunction "COM_COM") (pintype "bidirectional"))
      (node (ref "U1") (pin "4") (pinfunction "VCC_4") (pintype "bidirectional"))
    )
    (net (code "2") (name "/ADC_IN") (class "Default")
      (node (ref "IC3") (pin "35") (pinfunction "PB0_35") (pintype "bidirectional"))
      (node (ref "JP2") (pin "8") (pinfunction "8_8") (pintype "passive"))
    )
    (net (code "3") (name "/ADC_LIGHT") (class "Default")
      (node (ref "C13") (pin "2") (pinfunction "2_2") (pintype "passive"))
      (node (ref "IC3") (pin "36") (pinfunction "PB1_36") (pintype "bidirectional"))
      (node (ref "LED4") (pin "A") (pinfunction "A_A") (pintype "passive"))
      (node (ref "R5") (pin "1") (pinfunction "1_1") (pintype "passive"))
    )
    (net (code "4") (name "/ADC_VIN") (class "Default")
      (node (ref "C18") (pin "2") (pinfunction "2_2") (pintype "passive"))
      (node (ref "IC3") (pin "26") (pinfunction "PA3_26") (pintype "bidirectional"))
      (node (ref "R3") (pin "2") (pinfunction "2_2") (pintype "passive"))
      (node (ref "R4") (pin "1") (pinfunction "1_1") (pintype "passive"))
    )
    (net (code "5") (name "/ADC_X") (class "Default")
      (node (ref "IC3") (pin "17") (pinfunction "PC2_17") (pintype "bidirectional"))
      (node (ref "J2") (pin "46") (pinfunction "X-_46") (pintype "passive"))
    )
    (net (code "6") (name "/ADC_Y") (class "Default")
      (node (ref "IC3") (pin "18") (pinfunction "PC3_18") (pintype "bidirectional"))
      (node (ref "J2") (pin "47") (pinfunction "Y-_47") (pintype "passive"))
    )
    (net (code "7") (name "/BAT") (class "Default")
      (node (ref "C48") (pin "2") (pinfunction "2_2") (pintype "passive"))
      (node (ref "IC7") (pin "5") (pinfunction "BAT_5") (pintype "input"))
      (node (ref "R51") (pin "1") (pinfunction "1_1") (pintype "passive"))
    )
    (net (code "8") (name "/BOOT0{slash}JOY_CEN") (class "Default")
      (node (ref "IC3") (pin "94") (pinfunction "BOOT0_94") (pintype "bidirectional"))
      (node (ref "IC3") (pin "97") (pinfunction "PE0_97") (pintype "bidirectional"))
      (node (ref "R33") (pin "2") (pinfunction "2_2") (pintype "passive"))
      (node (ref "SW1") (pin "CTR") (pinfunction "CENT_CTR") (pintype "bidirectional"))
    )
    (net (code "9") (name "/BTN_A") (class "Default")
      (node (ref "IC3") (pin "77") (pinfunction "PA15_77") (pintype "bidirectional"))
      (node (ref "S4") (pin "2") (pinfunction "2_2") (pintype "passive"))
      (node (ref "S4") (pin "B1") (pinfunction "2_B1") (pintype "passive"))
      (node (ref "S4") (pin "B2") (pinfunction "2_B2") (pintype "passive"))
    )
    (net (code "10") (name "/BTN_B") (class "Default")
      (node (ref "IC3") (pin "58") (pinfunction "PD11_58") (pintype "bidirectional"))
      (node (ref "S3") (pin "2") (pinfunction "2_2") (pintype "passive"))
      (node (ref "S3") (pin "B1") (pinfunction "2_B1") (pintype "passive"))
      (node (ref "S3") (pin "B2") (pinfunction "2_B2") (pintype "passive"))
    )
    (net (code "11") (name "/BTN_MENU") (class "Default")
      (node (ref "IC3") (pin "84") (pinfunction "PD3_84") (pintype "bidirectional"))
      (node (ref "S7") (pin "P$2") (pinfunction "2_P$2") (pintype "passive"))
    )
    (net (code "12") (name "/BUZZ") (class "Default")
      (node (ref "IC3") (pin "59") (pinfunction "PD12_59") (pintype "bidirectional"))
      (node (ref "R26") (pin "2") (pinfunction "2_2") (pintype "passive"))
    )
    (net (code "13") (name "/C1") (class "Default")
      (node (ref "C40") (pin "1") (pinfunction "1_1") (pintype "passive"))
      (node (ref "IC9") (pin "4") (pinfunction "C1_4") (pintype "bidirectional"))
    )
    (net (code "14") (name "/CC_IRQ") (class "Default")
      (node (ref "IC3") (pin "3") (pinfunction "PE4_3") (pintype "bidirectional"))
      (node (ref "IC6") (pin "11") (pinfunction "IRQ_11") (pintype "output"))
    )
    (net (code "15") (name "/CC_RESERVED") (class "Default")
      (node (ref "IC6") (pin "21") (pinfunction "RESERVED_21") (pintype "input"))
      (node (ref "R20") (pin "1") (pinfunction "1_1") (pintype "passive"))
    )
    (net (code "16") (name "/COUT") (class "Default")
      (node (ref "IC7") (pin "2") (pinfunction "COUT_2") (pintype "output"))
      (node (ref "Q4") (pin "5") (pinfunction "G_5") (pintype "bidirectional"))
      (node (ref "R28") (pin "1") (pinfunction "1_1") (pintype "passive"))
    )
    (net (code "17") (name "/DAC_OUT") (class "Default")
      (node (ref "IC3") (pin "30") (pinfunction "PA5_30") (pintype "bidirectional"))
      (node (ref "JP2") (pin "5") (pinfunction "5_5") (pintype "passive"))
    )
    (net (code "18") (name "/DOUT") (class "Default")
      (node (ref "IC7") (pin "3") (pinfunction "DOUT_3") (pintype "output"))
      (node (ref "Q4") (pin "2") (pinfunction "G_2") (pintype "bidirectional"))
      (node (ref "R29") (pin "1") (pinfunction "1_1") (pintype "passive"))
    )
    (net (code "19") (name "/DRDY") (class "Default")
      (node (ref "IC8") (pin "9") (pinfunction "INT2_9") (pintype "output"))
      (node (ref "IC9") (pin "8") (pinfunction "DRDY_8") (pintype "output"))
    )
    (net (code "20") (name "/D_N") (class "Default")
      (node (ref "IC1") (pin "1") (pinfunction "IO1_1") (pintype "bidirectional"))
      (node (ref "IC3") (pin "70") (pinfunction "PA11_70") (pintype "bidirectional"))
      (node (ref "J1") (pin "D-") (pinfunction "D-_D-") (pintype "bidirectional"))
    )
    (net (code "21") (name "/D_P") (class "Default")
      (node (ref "IC1") (pin "2") (pinfunction "IO2_2") (pintype "bidirectional"))
      (node (ref "IC3") (pin "71") (pinfunction "PA12_71") (pintype "bidirectional"))
      (node (ref "J1") (pin "D+") (pinfunction "D+_D+") (pintype "bidirectional"))
    )
    (net (code "22") (name "/FET_OUT") (class "Default")
      (node (ref "LED1") (pin "K") (pinfunction "C_K") (pintype "passive"))
      (node (ref "OUTLINE1") (pin "FET") (pinfunction "FET_FET") (pintype "bidirectional"))
      (node (ref "Q3") (pin "1") (pinfunction "D_1") (pintype "bidirectional"))
      (node (ref "Q3") (pin "2") (pinfunction "D_2") (pintype "bidirectional"))
      (node (ref "Q3") (pin "5") (pinfunction "D_5") (pintype "bidirectional"))
      (node (ref "Q3") (pin "6") (pinfunction "D_6") (pintype "bidirectional"))
      (node (ref "Q3") (pin "EP1") (pinfunction "D_EP1") (pintype "bidirectional"))
    )
    (net (code "23") (name "/FORCE_AP") (class "Default")
      (node (ref "IC6") (pin "10") (pinfunction "FORCE_AP_10") (pintype "bidirectional"))
      (node (ref "R27") (pin "1") (pinfunction "1_1") (pintype "passive"))
      (node (ref "TP11") (pin "TP") (pinfunction "TP_TP") (pintype "input"))
    )
    (net (code "24") (name "/FSMC_A23") (class "Default")
      (node (ref "IC3") (pin "1") (pinfunction "PE2_1") (pintype "bidirectional"))
      (node (ref "IC3") (pin "89") (pinfunction "PB3_89") (pintype "bidirectional"))
      (node (ref "J2") (pin "37") (pinfunction "D/CX(SCL)_37") (pintype "input"))
      (node (ref "TP4") (pin "TP") (pinfunction "TP_TP") (pintype "input"))
    )
    (net (code "25") (name "/FS_VUSB") (class "Default")
      (node (ref "IC3") (pin "68") (pinfunction "PA9_68") (pintype "bidirectional"))
      (node (ref "R10") (pin "1") (pinfunction "1_1") (pintype "passive"))
    )
    (net (code "26") (name "/I2C_SCL") (class "Default")
      (node (ref "IC3") (pin "95") (pinfunction "PB8_95") (pintype "bidirectional"))
      (node (ref "JP2") (pin "4") (pinfunction "4_4") (pintype "passive"))
      (node (ref "OUTLINE1") (pin "SCL") (pinfunction "SCL_SCL") (pintype "bidirectional"))
    )
    (net (code "27") (name "/I2C_SDA") (class "Default")
      (node (ref "IC3") (pin "96") (pinfunction "PB9_96") (pintype "bidirectional"))
      (node (ref "JP2") (pin "3") (pinfunction "3_3") (pintype "passive"))
      (node (ref "OUTLINE1") (pin "SDA") (pinfunction "SDA_SDA") (pintype "bidirectional"))
    )
    (net (code "28") (name "/IMU_IRQ2") (class "Default")
      (node (ref "IC3") (pin "7") (pinfunction "PC13_7") (pintype "bidirectional"))
      (node (ref "IC8") (pin "4") (pinfunction "INT1_4") (pintype "output"))
    )
    (net (code "29") (name "/IMU_SCL") (class "Default")
      (node (ref "IC3") (pin "15") (pinfunction "PC0_15") (pintype "bidirectional"))
      (node (ref "IC8") (pin "13") (pinfunction "SCL_13") (pintype "input"))
      (node (ref "R19") (pin "2") (pinfunction "2_2") (pintype "passive"))
      (node (ref "TP19") (pin "TP") (pinfunction "TP_TP") (pintype "input"))
    )
    (net (code "30") (name "/IMU_SDA") (class "Default")
      (node (ref "IC3") (pin "16") (pinfunction "PC1_16") (pintype "bidirectional"))
      (node (ref "IC8") (pin "14") (pinfunction "SDA_14") (pintype "open_collector"))
      (node (ref "R18") (pin "2") (pinfunction "2_2") (pintype "passive"))
      (node (ref "TP18") (pin "TP") (pinfunction "TP_TP") (pintype "input"))
    )
    (net (code "31") (name "/JOY_DOWN") (class "Default")
      (node (ref "IC3") (pin "56") (pinfunction "PD9_56") (pintype "bidirectional"))
      (node (ref "SW1") (pin "D") (pinfunction "DOWN_D") (pintype "bidirectional"))
    )
    (net (code "32") (name "/JOY_LEFT") (class "Default")
      (node (ref "IC3") (pin "87") (pinfunction "PD6_87") (pintype "bidirectional"))
      (node (ref "SW1") (pin "C") (pinfunction "LEFT_C") (pintype "bidirectional"))
    )
    (net (code "33") (name "/JOY_RIGHT") (class "Default")
      (node (ref "IC3") (pin "57") (pinfunction "PD10_57") (pintype "bidirectional"))
      (node (ref "SW1") (pin "B") (pinfunction "RIGHT_B") (pintype "bidirectional"))
    )
    (net (code "34") (name "/JOY_UP") (class "Default")
      (node (ref "IC3") (pin "55") (pinfunction "PD8_55") (pintype "bidirectional"))
      (node (ref "SW1") (pin "A") (pinfunction "UP_A") (pintype "bidirectional"))
    )
    (net (code "35") (name "/LCD0") (class "Default")
      (node (ref "IC3") (pin "61") (pinfunction "PD14_61") (pintype "bidirectional"))
      (node (ref "J2") (pin "32") (pinfunction "DB0_32") (pintype "bidirectional"))
      (node (ref "TP1") (pin "TP") (pinfunction "TP_TP") (pintype "input"))
    )
    (net (code "36") (name "/LCD1") (class "Default")
      (node (ref "IC3") (pin "62") (pinfunction "PD15_62") (pintype "bidirectional"))
      (node (ref "J2") (pin "31") (pinfunction "DB1_31") (pintype "bidirectional"))
    )
    (net (code "37") (name "/LCD2") (class "Default")
      (node (ref "IC3") (pin "81") (pinfunction "PD0_81") (pintype "bidirectional"))
      (node (ref "J2") (pin "30") (pinfunction "DB2_30") (pintype "bidirectional"))
    )
    (net (code "38") (name "/LCD3") (class "Default")
      (node (ref "IC3") (pin "82") (pinfunction "PD1_82") (pintype "bidirectional"))
      (node (ref "J2") (pin "29") (pinfunction "DB3_29") (pintype "bidirectional"))
    )
    (net (code "39") (name "/LCD4") (class "Default")
      (node (ref "IC3") (pin "38") (pinfunction "PE7_38") (pintype "bidirectional"))
      (node (ref "J2") (pin "28") (pinfunction "DB4_28") (pintype "bidirectional"))
    )
    (net (code "40") (name "/LCD5") (class "Default")
      (node (ref "IC3") (pin "39") (pinfunction "PE8_39") (pintype "bidirectional"))
      (node (ref "J2") (pin "27") (pinfunction "DB5_27") (pintype "bidirectional"))
    )
    (net (code "41") (name "/LCD6") (class "Default")
      (node (ref "IC3") (pin "40") (pinfunction "PE9_40") (pintype "bidirectional"))
      (node (ref "J2") (pin "26") (pinfunction "DB6_26") (pintype "bidirectional"))
    )
    (net (code "42") (name "/LCD7") (class "Default")
      (node (ref "IC3") (pin "41") (pinfunction "PE10_41") (pintype "bidirectional"))
      (node (ref "J2") (pin "25") (pinfunction "DB7_25") (pintype "bidirectional"))
    )
    (net (code "43") (name "/LCD_CS") (class "Default")
      (node (ref "IC3") (pin "88") (pinfunction "PD7_88") (pintype "bidirectional"))
      (node (ref "J2") (pin "38") (pinfunction "CSX_38") (pintype "output"))
    )
    (net (code "44") (name "/LCD_MODE") (class "Default")
      (node (ref "IC3") (pin "5") (pinfunction "PE6_5") (pintype "bidirectional"))
      (node (ref "J2") (pin "7") (pinfunction "IM1_7") (pintype "input"))
      (node (ref "J2") (pin "8") (pinfunction "IM2_8") (pintype "input"))
      (node (ref "J2") (pin "9") (pinfunction "IM3_9") (pintype "input"))
    )
    (net (code "45") (name "/LCD_RD") (class "Default")
      (node (ref "IC3") (pin "85") (pinfunction "PD4_85") (pintype "bidirectional"))
      (node (ref "J2") (pin "35") (pinfunction "RD_35") (pintype "input"))
      (node (ref "TP2") (pin "TP") (pinfunction "TP_TP") (pintype "input"))
    )
    (net (code "46") (name "/LCD_WRX") (class "Default")
      (node (ref "IC3") (pin "86") (pinfunction "PD5_86") (pintype "bidirectional"))
      (node (ref "J2") (pin "36") (pinfunction "WRX(D/CX)_36") (pintype "input"))
      (node (ref "TP3") (pin "TP") (pinfunction "TP_TP") (pintype "input"))
    )
    (net (code "47") (name "/LCD_~{RST}") (class "Default")
      (node (ref "IC3") (pin "60") (pinfunction "PD13_60") (pintype "bidirectional"))
      (node (ref "J2") (pin "10") (pinfunction "RESET_10") (pintype "input"))
    )
    (net (code "48") (name "/LED1") (class "Default")
      (node (ref "IC3") (pin "46") (pinfunction "PE15_46") (pintype "bidirectional"))
      (node (ref "R12") (pin "2") (pinfunction "2_2") (pintype "passive"))
    )
    (net (code "49") (name "/LED2") (class "Default")
      (node (ref "IC3") (pin "43") (pinfunction "PE12_43") (pintype "bidirectional"))
      (node (ref "R14") (pin "2") (pinfunction "2_2") (pintype "passive"))
    )
    (net (code "50") (name "/NRST") (class "Default")
      (node (ref "IC3") (pin "14") (pinfunction "~{NRST}_14") (pintype "bidirectional"))
      (node (ref "J3") (pin "10") (pinfunction "NRST_10") (pintype "bidirectional"))
      (node (ref "JP4") (pin "3") (pinfunction "RST_3") (pintype "output"))
      (node (ref "S1") (pin "P$1") (pinfunction "1_P$1") (pintype "passive"))
    )
    (net (code "51") (name "/OCS32_IN") (class "Default")
      (node (ref "C23") (pin "2") (pinfunction "2_2") (pintype "passive"))
      (node (ref "IC3") (pin "8") (pinfunction "PC14/OSC32_IN_8") (pintype "bidirectional"))
      (node (ref "X3") (pin "P$1") (pinfunction "1_P$1") (pintype "bidirectional"))
    )
    (net (code "52") (name "/OCS32_OUT") (class "Default")
      (node (ref "C24") (pin "2") (pinfunction "2_2") (pintype "passive"))
      (node (ref "IC3") (pin "9") (pinfunction "PC15/OSC32_OUT_9") (pintype "bidirectional"))
      (node (ref "X3") (pin "P$2") (pinfunction "2_P$2") (pintype "bidirectional"))
    )
    (net (code "53") (name "/PB2") (class "Default")
      (node (ref "IC3") (pin "37") (pinfunction "PB2_37") (pintype "bidirectional"))
      (node (ref "JP1") (pin "7") (pinfunction "7_7") (pintype "passive"))
      (node (ref "R11") (pin "2") (pinfunction "2_2") (pintype "passive"))
    )
    (net (code "54") (name "/SCX") (class "Default")
      (node (ref "IC8") (pin "3") (pinfunction "SCX_3") (pintype "input"))
      (node (ref "IC9") (pin "1") (pinfunction "SCL/SPC_1") (pintype "input"))
      (node (ref "R31") (pin "2") (pinfunction "2_2") (pintype "passive"))
    )
    (net (code "55") (name "/SDIO_CLK") (class "Default")
      (node (ref "IC3") (pin "80") (pinfunction "PC12_80") (pintype "bidirectional"))
      (node (ref "U1") (pin "5") (pinfunction "CLK_5") (pintype "bidirectional"))
    )
    (net (code "56") (name "/SDIO_CMD") (class "Default")
      (node (ref "IC3") (pin "83") (pinfunction "PD2_83") (pintype "bidirectional"))
      (node (ref "U1") (pin "3") (pinfunction "CMD_3") (pintype "bidirectional"))
    )
    (net (code "57") (name "/SDIO_D0") (class "Default")
      (node (ref "IC3") (pin "65") (pinfunction "PC8_65") (pintype "bidirectional"))
      (node (ref "U1") (pin "7") (pinfunction "DAT0_7") (pintype "bidirectional"))
    )
    (net (code "58") (name "/SDIO_D1") (class "Default")
      (node (ref "IC3") (pin "66") (pinfunction "PC9_66") (pintype "bidirectional"))
      (node (ref "U1") (pin "8") (pinfunction "DAT1_8") (pintype "bidirectional"))
    )
    (net (code "59") (name "/SDIO_D2") (class "Default")
      (node (ref "IC3") (pin "78") (pinfunction "PC10_78") (pintype "bidirectional"))
      (node (ref "U1") (pin "1") (pinfunction "DAT2_1") (pintype "bidirectional"))
    )
    (net (code "60") (name "/SDIO_D3") (class "Default")
      (node (ref "IC3") (pin "79") (pinfunction "PC11_79") (pintype "bidirectional"))
      (node (ref "U1") (pin "2") (pinfunction "DAT3_2") (pintype "bidirectional"))
    )
    (net (code "61") (name "/SDIO_SW") (class "Default")
      (node (ref "IC3") (pin "67") (pinfunction "PA8_67") (pintype "bidirectional"))
      (node (ref "U1") (pin "CD") (pinfunction "DET_CD") (pintype "bidirectional"))
    )
    (net (code "62") (name "/SDX") (class "Default")
      (node (ref "IC8") (pin "2") (pinfunction "SDX_2") (pintype "input"))
      (node (ref "IC9") (pin "11") (pinfunction "SDA/SDI/SDO_11") (pintype "bidirectional"))
      (node (ref "R30") (pin "2") (pinfunction "2_2") (pintype "passive"))
    )
    (net (code "63") (name "/SPI1_MISO") (class "Default")
      (node (ref "IC3") (pin "31") (pinfunction "PA6_31") (pintype "bidirectional"))
      (node (ref "IC6") (pin "7") (pinfunction "SPI_DOUT_7") (pintype "output"))
    )
    (net (code "64") (name "/SPI1_MOSI") (class "Default")
      (node (ref "IC3") (pin "32") (pinfunction "PA7_32") (pintype "bidirectional"))
      (node (ref "IC6") (pin "6") (pinfunction "SPI_DIN_6") (pintype "input"))
    )
    (net (code "65") (name "/SPI1_NSS") (class "Default")
      (node (ref "IC3") (pin "29") (pinfunction "PA4_29") (pintype "bidirectional"))
      (node (ref "IC6") (pin "8") (pinfunction "~{SPI_CS}_8") (pintype "input"))
    )
    (net (code "66") (name "/SPI1_SCK") (class "Default")
      (node (ref "IC3") (pin "44") (pinfunction "PE13_44") (pintype "bidirectional"))
      (node (ref "IC6") (pin "5") (pinfunction "SPI_CLK_5") (pintype "input"))
    )
    (net (code "67") (name "/SPI2_CLK") (class "Default")
      (node (ref "IC3") (pin "47") (pinfunction "PB10_47") (pintype "bidirectional"))
      (node (ref "JP1") (pin "8") (pinfunction "8_8") (pintype "passive"))
    )
    (net (code "68") (name "/SPI2_MISO") (class "Default")
      (node (ref "IC3") (pin "53") (pinfunction "PB14_53") (pintype "bidirectional"))
      (node (ref "JP1") (pin "9") (pinfunction "9_9") (pintype "passive"))
    )
    (net (code "69") (name "/SPI2_MOSI") (class "Default")
      (node (ref "IC3") (pin "54") (pinfunction "PB15_54") (pintype "bidirectional"))
      (node (ref "JP1") (pin "10") (pinfunction "10_10") (pintype "passive"))
    )
    (net (code "70") (name "/SPI2_NSS") (class "Default")
      (node (ref "IC3") (pin "51") (pinfunction "PB12_51") (pintype "bidirectional"))
      (node (ref "JP1") (pin "6") (pinfunction "6_6") (pintype "passive"))
    )
    (net (code "71") (name "/SPI3_MISO") (class "Default")
      (node (ref "IC3") (pin "90") (pinfunction "PB4_90") (pintype "bidirectional"))
      (node (ref "J2") (pin "33") (pinfunction "SDO_33") (pintype "output"))
    )
    (net (code "72") (name "/SPI3_MOSI") (class "Default")
      (node (ref "IC3") (pin "91") (pinfunction "PB5_91") (pintype "bidirectional"))
      (node (ref "J2") (pin "34") (pinfunction "SDI_34") (pintype "input"))
    )
    (net (code "73") (name "/SWCLK") (class "Default")
      (node (ref "IC3") (pin "76") (pinfunction "PA14_76") (pintype "bidirectional"))
      (node (ref "J3") (pin "4") (pinfunction "SWCLK_4") (pintype "bidirectional"))
      (node (ref "JP4") (pin "4") (pinfunction "SWCLK_4") (pintype "output"))
    )
    (net (code "74") (name "/SWDAT") (class "Default")
      (node (ref "IC3") (pin "72") (pinfunction "PA13_72") (pintype "bidirectional"))
      (node (ref "J3") (pin "2") (pinfunction "SWDAT_2") (pintype "bidirectional"))
      (node (ref "JP4") (pin "2") (pinfunction "SWDAT_2") (pintype "bidirectional"))
    )
    (net (code "75") (name "/TEAR") (class "Default")
      (node (ref "IC3") (pin "4") (pinfunction "PE5_4") (pintype "bidirectional"))
      (node (ref "J2") (pin "39") (pinfunction "TE_39") (pintype "output"))
      (node (ref "TP21") (pin "TP") (pinfunction "TP_TP") (pintype "input"))
    )
    (net (code "76") (name "/TIM1_CH2") (class "Default")
      (node (ref "IC3") (pin "42") (pinfunction "PE11_42") (pintype "bidirectional"))
      (node (ref "JP2") (pin "9") (pinfunction "9_9") (pintype "passive"))
    )
    (net (code "77") (name "/TIM1_CH4") (class "Default")
      (node (ref "IC3") (pin "45") (pinfunction "PE14_45") (pintype "bidirectional"))
      (node (ref "JP2") (pin "10") (pinfunction "10_10") (pintype "passive"))
    )
    (net (code "78") (name "/TIM2_CH1") (class "Default")
      (node (ref "IC3") (pin "23") (pinfunction "PA0_23") (pintype "bidirectional"))
      (node (ref "JP1") (pin "2") (pinfunction "2_2") (pintype "passive"))
      (node (ref "OUTLINE1") (pin "CH4") (pinfunction "CH4_CH4") (pintype "bidirectional"))
      (node (ref "SV3") (pin "3") (pinfunction "3_3") (pintype "passive"))
    )
    (net (code "79") (name "/TIM2_CH2") (class "Default")
      (node (ref "IC3") (pin "24") (pinfunction "PA1_24") (pintype "bidirectional"))
      (node (ref "JP1") (pin "3") (pinfunction "3_3") (pintype "passive"))
      (node (ref "OUTLINE1") (pin "CH3") (pinfunction "CH3_CH3") (pintype "bidirectional"))
      (node (ref "SV5") (pin "3") (pinfunction "3_3") (pintype "passive"))
    )
    (net (code "80") (name "/TIM2_CH3") (class "Default")
      (node (ref "IC3") (pin "25") (pinfunction "PA2_25") (pintype "bidirectional"))
      (node (ref "JP1") (pin "4") (pinfunction "4_4") (pintype "passive"))
      (node (ref "OUTLINE1") (pin "CH2") (pinfunction "CH2_CH2") (pintype "bidirectional"))
      (node (ref "SV6") (pin "3") (pinfunction "3_3") (pintype "passive"))
    )
    (net (code "81") (name "/TIM2_CH4") (class "Default")
      (node (ref "C9") (pin "2") (pinfunction "2_2") (pintype "passive"))
      (node (ref "IC3") (pin "48") (pinfunction "VCAP1_48") (pintype "bidirectional"))
      (node (ref "JP1") (pin "5") (pinfunction "5_5") (pintype "passive"))
      (node (ref "OUTLINE1") (pin "CH1") (pinfunction "CH1_CH1") (pintype "bidirectional"))
      (node (ref "SV4") (pin "3") (pinfunction "3_3") (pintype "passive"))
    )
    (net (code "82") (name "/TIM8_CH2") (class "Default")
      (node (ref "IC3") (pin "64") (pinfunction "PC7_64") (pintype "bidirectional"))
      (node (ref "Q3") (pin "3") (pinfunction "G_3") (pintype "bidirectional"))
    )
    (net (code "83") (name "/TIM17_CH1") (class "Default")
      (node (ref "IC3") (pin "98") (pinfunction "PE1_98") (pintype "bidirectional"))
      (node (ref "Q8") (pin "3") (pinfunction "G_3") (pintype "bidirectional"))
    )
    (net (code "84") (name "/T_X") (class "Default")
      (node (ref "IC3") (pin "12") (pinfunction "PH0/OCS_IN_12") (pintype "bidirectional"))
      (node (ref "J2") (pin "44") (pinfunction "X+_44") (pintype "passive"))
    )
    (net (code "85") (name "/T_Y") (class "Default")
      (node (ref "IC3") (pin "13") (pinfunction "PH1/OSC_OUT_13") (pintype "bidirectional"))
      (node (ref "J2") (pin "45") (pinfunction "Y+_45") (pintype "passive"))
    )
    (net (code "86") (name "/USART1_RX") (class "Default")
      (node (ref "IC3") (pin "93") (pinfunction "PB7_93") (pintype "bidirectional"))
      (node (ref "IC6") (pin "46") (pinfunction "UART1_TX_46") (pintype "output"))
      (node (ref "SV7") (pin "3") (pinfunction "3_3") (pintype "passive"))
    )
    (net (code "87") (name "/USART1_TX") (class "Default")
      (node (ref "IC3") (pin "92") (pinfunction "PB6_92") (pintype "bidirectional"))
      (node (ref "IC6") (pin "47") (pinfunction "UART1_RX_47") (pintype "input"))
      (node (ref "SV7") (pin "2") (pinfunction "2_2") (pintype "passive"))
    )
    (net (code "88") (name "/USART3_RX") (class "Default")
      (node (ref "IC3") (pin "34") (pinfunction "PC5_34") (pintype "bidirectional"))
      (node (ref "JP2") (pin "7") (pinfunction "7_7") (pintype "passive"))
    )
    (net (code "89") (name "/USART3_TX") (class "Default")
      (node (ref "IC3") (pin "33") (pinfunction "PC4_33") (pintype "bidirectional"))
      (node (ref "JP2") (pin "6") (pinfunction "6_6") (pintype "passive"))
    )
    (net (code "90") (name "/USB_ID") (class "Default")
      (node (ref "IC1") (pin "4") (pinfunction "IO3_4") (pintype "bidirectional"))
      (node (ref "IC3") (pin "69") (pinfunction "PA10_69") (pintype "bidirectional"))
      (node (ref "J1") (pin "ID") (pinfunction "USBID_ID") (pintype "bidirectional"))
    )
    (net (code "91") (name "/V-") (class "Default")
      (node (ref "IC7") (pin "6") (pinfunction "V-_6") (pintype "input"))
      (node (ref "R50") (pin "1") (pinfunction "1_1") (pintype "passive"))
    )
    (net (code "92") (name "/VACP2") (class "Default")
      (node (ref "C29") (pin "2") (pinfunction "2_2") (pintype "passive"))
      (node (ref "IC3") (pin "73") (pinfunction "VCAP2_73") (pintype "bidirectional"))
      (node (ref "R7") (pin "2") (pinfunction "2_2") (pintype "passive"))
    )
    (net (code "93") (name "/VBATT_IN") (class "Default")
      (node (ref "C33") (pin "2") (pinfunction "2_2") (pintype "passive"))
      (node (ref "IC3") (pin "6") (pinfunction "VBAT_6") (pintype "bidirectional"))
      (node (ref "R21") (pin "1") (pinfunction "1_1") (pintype "passive"))
      (node (ref "R22") (pin "1") (pinfunction "1_1") (pintype "passive"))
    )
    (net (code "94") (name "/VBAT_NEG") (class "Default")
      (node (ref "C48") (pin "1") (pinfunction "1_1") (pintype "passive"))
      (node (ref "IC7") (pin "4") (pinfunction "VSS_4") (pintype "power_in"))
      (node (ref "JP3") (pin "1") (pinfunction "1_1") (pintype "passive"))
      (node (ref "Q4") (pin "1") (pinfunction "S_1") (pintype "bidirectional"))
      (node (ref "R29") (pin "2") (pinfunction "2_2") (pintype "passive"))
      (node (ref "R32") (pin "2") (pinfunction "2_2") (pintype "passive"))
    )
    (net (code "95") (name "/V_UNREG") (class "Default")
      (node (ref "C2") (pin "2") (pinfunction "2_2") (pintype "passive"))
      (node (ref "C6") (pin "1") (pinfunction "1_1") (pintype "passive"))
      (node (ref "D1") (pin "1") (pinfunction "VDD_1") (pintype "power_in"))
      (node (ref "D3") (pin "C") (pinfunction "C_C") (pintype "passive"))
      (node (ref "IC2") (pin "1") (pinfunction "EN_1") (pintype "input"))
      (node (ref "IC2") (pin "8") (pinfunction "VIN_8") (pintype "power_in"))
      (node (ref "JP2") (pin "2") (pinfunction "2_2") (pintype "passive"))
      (node (ref "OUTLINE1") (pin "VBATT") (pinfunction "VBATT_VBATT") (pintype "bidirectional"))
      (node (ref "Q1") (pin "5") (pinfunction "E2_5") (pintype "passive"))
      (node (ref "Q2") (pin "5") (pinfunction "S_5") (pintype "bidirectional"))
      (node (ref "Q2") (pin "6") (pinfunction "S_6") (pintype "bidirectional"))
      (node (ref "Q2") (pin "7") (pinfunction "S_7") (pintype "bidirectional"))
      (node (ref "Q2") (pin "8") (pinfunction "S_8") (pintype "bidirectional"))
      (node (ref "Q2") (pin "EP") (pinfunction "S_EP") (pintype "bidirectional"))
      (node (ref "R3") (pin "1") (pinfunction "1_1") (pintype "passive"))
      (node (ref "SV2") (pin "2") (pinfunction "2_2") (pintype "passive"))
      (node (ref "SV3") (pin "2") (pinfunction "2_2") (pintype "passive"))
      (node (ref "SV4") (pin "2") (pinfunction "2_2") (pintype "passive"))
      (node (ref "SV5") (pin "2") (pinfunction "2_2") (pintype "passive"))
      (node (ref "SV6") (pin "2") (pinfunction "2_2") (pintype "passive"))
    )
    (net (code "96") (name "/WS2812") (class "Default")
      (node (ref "D1") (pin "4") (pinfunction "DIN_4") (pintype "input"))
      (node (ref "IC3") (pin "52") (pinfunction "PB13_52") (pintype "bidirectional"))
    )
    (net (code "97") (name "/~{CC_HIB}") (class "Default")
      (node (ref "IC3") (pin "63") (pinfunction "PC6_63") (pintype "bidirectional"))
      (node (ref "IC6") (pin "4") (pinfunction "~{HIB}_4") (pintype "input"))
      (node (ref "TP5") (pin "TP") (pinfunction "TP_TP") (pintype "input"))
    )
    (net (code "98") (name "/~{CC_RST}") (class "Default")
      (node (ref "IC3") (pin "2") (pinfunction "PE3_2") (pintype "bidirectional"))
      (node (ref "IC6") (pin "35") (pinfunction "~{RESET}_35") (pintype "input"))
      (node (ref "S8") (pin "P$1") (pinfunction "1_P$1") (pintype "passive"))
      (node (ref "TP20") (pin "TP") (pinfunction "TP_TP") (pintype "input"))
    )
    (net (code "99") (name "GND") (class "Default")
      (node (ref "C1") (pin "1") (pinfunction "1_1") (pintype "passive"))
      (node (ref "C10") (pin "1") (pinfunction "1_1") (pintype "passive"))
      (node (ref "C11") (pin "1") (pinfunction "1_1") (pintype "passive"))
      (node (ref "C12") (pin "1") (pinfunction "1_1") (pintype "passive"))
      (node (ref "C13") (pin "1") (pinfunction "1_1") (pintype "passive"))
      (node (ref "C15") (pin "1") (pinfunction "1_1") (pintype "passive"))
      (node (ref "C16") (pin "1") (pinfunction "1_1") (pintype "passive"))
      (node (ref "C17") (pin "1") (pinfunction "1_1") (pintype "passive"))
      (node (ref "C18") (pin "1") (pinfunction "1_1") (pintype "passive"))
      (node (ref "C19") (pin "1") (pinfunction "1_1") (pintype "passive"))
      (node (ref "C2") (pin "1") (pinfunction "1_1") (pintype "passive"))
      (node (ref "C22") (pin "1") (pinfunction "1_1") (pintype "passive"))
      (node (ref "C23") (pin "1") (pinfunction "1_1") (pintype "passive"))
      (node (ref "C24") (pin "1") (pinfunction "1_1") (pintype "passive"))
      (node (ref "C25") (pin "2") (pinfunction "2_2") (pintype "passive"))
      (node (ref "C26") (pin "2") (pinfunction "2_2") (pintype "passive"))
      (node (ref "C27") (pin "2") (pinfunction "2_2") (pintype "passive"))
      (node (ref "C29") (pin "1") (pinfunction "1_1") (pintype "passive"))
      (node (ref "C3") (pin "1") (pinfunction "1_1") (pintype "passive"))
      (node (ref "C33") (pin "1") (pinfunction "1_1") (pintype "passive"))
      (node (ref "C34") (pin "1") (pinfunction "1_1") (pintype "passive"))
      (node (ref "C35") (pin "2") (pinfunction "2_2") (pintype "passive"))
      (node (ref "C36") (pin "2") (pinfunction "2_2") (pintype "passive"))
      (node (ref "C37") (pin "1") (pinfunction "1_1") (pintype "passive"))
      (node (ref "C38") (pin "1") (pinfunction "1_1") (pintype "passive"))
      (node (ref "C39") (pin "1") (pinfunction "1_1") (pintype "passive"))
      (node (ref "C4") (pin "-") (pinfunction "-_-") (pintype "passive"))
      (node (ref "C40") (pin "2") (pinfunction "2_2") (pintype "passive"))
      (node (ref "C41") (pin "2") (pinfunction "2_2") (pintype "passive"))
      (node (ref "C42") (pin "2") (pinfunction "2_2") (pintype "passive"))
      (node (ref "C45") (pin "1") (pinfunction "1_1") (pintype "passive"))
      (node (ref "C5") (pin "2") (pinfunction "2_2") (pintype "passive"))
      (node (ref "C6") (pin "2") (pinfunction "2_2") (pintype "passive"))
      (node (ref "C7") (pin "1") (pinfunction "1_1") (pintype "passive"))
      (node (ref "C8") (pin "1") (pinfunction "1_1") (pintype "passive"))
      (node (ref "C9") (pin "1") (pinfunction "1_1") (pintype "passive"))
      (node (ref "D1") (pin "3") (pinfunction "VSS_3") (pintype "power_in"))
      (node (ref "IC1") (pin "3") (pinfunction "GND_3") (pintype "power_in"))
      (node (ref "IC2") (pin "2") (pinfunction "GND_2") (pintype "power_in"))
      (node (ref "IC2") (pin "3") (pinfunction "MODE_3") (pintype "input"))
      (node (ref "IC2") (pin "EP") (pinfunction "GND_EP") (pintype "power_in"))
      (node (ref "IC3") (pin "10") (pinfunction "VSS1_10") (pintype "bidirectional"))
      (node (ref "IC3") (pin "20") (pinfunction "VSSA/VREF-_20") (pintype "bidirectional"))
      (node (ref "IC3") (pin "27") (pinfunction "VSS2_27") (pintype "bidirectional"))
      (node (ref "IC3") (pin "74") (pinfunction "VSS3_74") (pintype "bidirectional"))
      (node (ref "IC3") (pin "99") (pinfunction "VSS4_99") (pintype "bidirectional"))
      (node (ref "IC4") (pin "3") (pinfunction "VSS_3") (pintype "power_in"))
      (node (ref "IC4") (pin "7") (pinfunction "ISET2_7") (pintype "input"))
      (node (ref "IC4") (pin "EP") (pinfunction "VSS_EP") (pintype "power_in"))
      (node (ref "IC6") (pin "1") (pinfunction "GND_1") (pintype "power_in"))
      (node (ref "IC6") (pin "16") (pinfunction "GND_16") (pintype "power_in"))
      (node (ref "IC6") (pin "2") (pinfunction "GND_2") (pintype "power_in"))
      (node (ref "IC6") (pin "27") (pinfunction "GND_27") (pintype "power_in"))
      (node (ref "IC6") (pin "28") (pinfunction "GND_28") (pintype "power_in"))
      (node (ref "IC6") (pin "30") (pinfunction "GND_30") (pintype "power_in"))
      (node (ref "IC6") (pin "32") (pinfunction "GND_32") (pintype "power_in"))
      (node (ref "IC6") (pin "38") (pinfunction "GND_38") (pintype "power_in"))
      (node (ref "IC6") (pin "43") (pinfunction "GND_43") (pintype "power_in"))
      (node (ref "IC6") (pin "55") (pinfunction "GND_55") (pintype "power_in"))
      (node (ref "IC6") (pin "56") (pinfunction "GND_56") (pintype "power_in"))
      (node (ref "IC6") (pin "57") (pinfunction "GND_57") (pintype "power_in"))
      (node (ref "IC6") (pin "58") (pinfunction "GND_58") (pintype "power_in"))
      (node (ref "IC6") (pin "59") (pinfunction "GND_59") (pintype "power_in"))
      (node (ref "IC6") (pin "60") (pinfunction "GND_60") (pintype "power_in"))
      (node (ref "IC6") (pin "61") (pinfunction "GND_61") (pintype "power_in"))
      (node (ref "IC6") (pin "62") (pinfunction "GND_62") (pintype "power_in"))
      (node (ref "IC6") (pin "63") (pinfunction "GND_63") (pintype "power_in"))
      (node (ref "IC8") (pin "1") (pinfunction "SDO/SA0_1") (pintype "bidirectional"))
      (node (ref "IC8") (pin "6") (pinfunction "GND_6") (pintype "power_in"))
      (node (ref "IC8") (pin "7") (pinfunction "GND_7") (pintype "power_in"))
      (node (ref "IC9") (pin "12") (pinfunction "GND_12") (pintype "power_in"))
      (node (ref "IC9") (pin "2") (pinfunction "GND_2") (pintype "power_in"))
      (node (ref "IC9") (pin "3") (pinfunction "GND_3") (pintype "power_in"))
      (node (ref "J1") (pin "GND") (pinfunction "GND_GND") (pintype "bidirectional"))
      (node (ref "J1") (pin "SHIELD") (pinfunction "SHIELD_SHIELD") (pintype "bidirectional"))
      (node (ref "J1") (pin "SHIELD@0") (pinfunction "SHIELD_SHIELD@0") (pintype "bidirectional"))
      (node (ref "J1") (pin "SHIELD@1") (pinfunction "SHIELD_SHIELD@1") (pintype "bidirectional"))
      (node (ref "J1") (pin "SHIELD@2") (pinfunction "SHIELD_SHIELD@2") (pintype "bidirectional"))
      (node (ref "J1") (pin "SHIELD@3") (pinfunction "SHIELD_SHIELD@3") (pintype "bidirectional"))
      (node (ref "J1") (pin "SHIELD@5") (pinfunction "SHIELD_SHIELD@5") (pintype "bidirectional"))
      (node (ref "J2") (pin "11") (pinfunction "VSYNC_11") (pintype "bidirectional"))
      (node (ref "J2") (pin "12") (pinfunction "HSYNC_12") (pintype "bidirectional"))
      (node (ref "J2") (pin "13") (pinfunction "DOTCLK_13") (pintype "bidirectional"))
      (node (ref "J2") (pin "14") (pinfunction "DE_14") (pintype "input"))
      (node (ref "J2") (pin "15") (pinfunction "DB17_15") (pintype "bidirectional"))
      (node (ref "J2") (pin "16") (pinfunction "DB16_16") (pintype "bidirectional"))
      (node (ref "J2") (pin "17") (pinfunction "DB15_17") (pintype "bidirectional"))
      (node (ref "J2") (pin "18") (pinfunction "DB14_18") (pintype "bidirectional"))
      (node (ref "J2") (pin "19") (pinfunction "DB13_19") (pintype "bidirectional"))
      (node (ref "J2") (pin "20") (pinfunction "DB12_20") (pintype "bidirectional"))
      (node (ref "J2") (pin "21") (pinfunction "DB11_21") (pintype "bidirectional"))
      (node (ref "J2") (pin "22") (pinfunction "DB10_22") (pintype "bidirectional"))
      (node (ref "J2") (pin "23") (pinfunction "DB9_23") (pintype "bidirectional"))
      (node (ref "J2") (pin "24") (pinfunction "DB8_24") (pintype "bidirectional"))
      (node (ref "J2") (pin "43") (pinfunction "GND_43") (pintype "power_in"))
      (node (ref "J2") (pin "48") (pinfunction "GND_48") (pintype "power_in"))
      (node (ref "J2") (pin "49") (pinfunction "GND_49") (pintype "power_in"))
      (node (ref "J2") (pin "50") (pinfunction "GND_50") (pintype "power_in"))
      (node (ref "J2") (pin "6") (pinfunction "IM0_6") (pintype "input"))
      (node (ref "J3") (pin "3") (pinfunction "GND1_3") (pintype "power_in"))
      (node (ref "J3") (pin "5") (pinfunction "GND2_5") (pintype "power_in"))
      (node (ref "J3") (pin "9") (pinfunction "GNDD_9") (pintype "power_in"))
      (node (ref "JP1") (pin "11") (pinfunction "11_11") (pintype "passive"))
      (node (ref "JP2") (pin "11") (pinfunction "11_11") (pintype "passive"))
      (node (ref "JP4") (pin "5") (pinfunction "GND_5") (pintype "power_in"))
      (node (ref "LED2") (pin "C") (pinfunction "C_C") (pintype "passive"))
      (node (ref "LED3") (pin "C") (pinfunction "C_C") (pintype "passive"))
      (node (ref "OUTLINE1") (pin "GND") (pinfunction "GND_GND") (pintype "bidirectional"))
      (node (ref "Q3") (pin "4") (pinfunction "S_4") (pintype "bidirectional"))
      (node (ref "Q3") (pin "EP2") (pinfunction "S_EP2") (pintype "bidirectional"))
      (node (ref "Q4") (pin "4") (pinfunction "S_4") (pintype "bidirectional"))
      (node (ref "Q8") (pin "4") (pinfunction "S_4") (pintype "bidirectional"))
      (node (ref "Q8") (pin "EP2") (pinfunction "S_EP2") (pintype "bidirectional"))
      (node (ref "R11") (pin "1") (pinfunction "1_1") (pintype "passive"))
      (node (ref "R13") (pin "2") (pinfunction "2_2") (pintype "passive"))
      (node (ref "R15") (pin "2") (pinfunction "2_2") (pintype "passive"))
      (node (ref "R16") (pin "2") (pinfunction "2_2") (pintype "passive"))
      (node (ref "R17") (pin "2") (pinfunction "2_2") (pintype "passive"))
      (node (ref "R20") (pin "2") (pinfunction "2_2") (pintype "passive"))
      (node (ref "R22") (pin "2") (pinfunction "2_2") (pintype "passive"))
      (node (ref "R27") (pin "2") (pinfunction "2_2") (pintype "passive"))
      (node (ref "R28") (pin "2") (pinfunction "2_2") (pintype "passive"))
      (node (ref "R32") (pin "1") (pinfunction "1_1") (pintype "passive"))
      (node (ref "R33") (pin "1") (pinfunction "1_1") (pintype "passive"))
      (node (ref "R4") (pin "2") (pinfunction "2_2") (pintype "passive"))
      (node (ref "R5") (pin "2") (pinfunction "2_2") (pintype "passive"))
      (node (ref "R50") (pin "2") (pinfunction "2_2") (pintype "passive"))
      (node (ref "R6") (pin "2") (pinfunction "2_2") (pintype "passive"))
      (node (ref "R9") (pin "2") (pinfunction "2_2") (pintype "passive"))
      (node (ref "S1") (pin "P$2") (pinfunction "2_P$2") (pintype "passive"))
      (node (ref "S3") (pin "1") (pinfunction "1_1") (pintype "passive"))
      (node (ref "S3") (pin "A1") (pinfunction "1_A1") (pintype "passive"))
      (node (ref "S3") (pin "A2") (pinfunction "1_A2") (pintype "passive"))
      (node (ref "S4") (pin "1") (pinfunction "1_1") (pintype "passive"))
      (node (ref "S4") (pin "A1") (pinfunction "1_A1") (pintype "passive"))
      (node (ref "S4") (pin "A2") (pinfunction "1_A2") (pintype "passive"))
      (node (ref "S5") (pin "2") (pinfunction "P_2") (pintype "passive"))
      (node (ref "S7") (pin "P$1") (pinfunction "1_P$1") (pintype "passive"))
      (node (ref "S8") (pin "P$2") (pinfunction "2_P$2") (pintype "passive"))
      (node (ref "SG1") (pin "P$2") (pinfunction "2_P$2") (pintype "passive"))
      (node (ref "SV2") (pin "1") (pinfunction "1_1") (pintype "passive"))
      (node (ref "SV3") (pin "1") (pinfunction "1_1") (pintype "passive"))
      (node (ref "SV4") (pin "1") (pinfunction "1_1") (pintype "passive"))
      (node (ref "SV5") (pin "1") (pinfunction "1_1") (pintype "passive"))
      (node (ref "SV6") (pin "1") (pinfunction "1_1") (pintype "passive"))
      (node (ref "SV7") (pin "1") (pinfunction "1_1") (pintype "passive"))
      (node (ref "U1") (pin "6") (pinfunction "GND_6") (pintype "bidirectional"))
      (node (ref "U1") (pin "GND") (pinfunction "SHIELD_GND") (pintype "bidirectional"))
      (node (ref "U1") (pin "GND1") (pinfunction "SHIELD_GND1") (pintype "bidirectional"))
      (node (ref "U1") (pin "GND2") (pinfunction "SHIELD_GND2") (pintype "bidirectional"))
      (node (ref "U1") (pin "GND3") (pinfunction "SHIELD_GND3") (pintype "bidirectional"))
    )
    (net (code "100") (name "Net-(ANT1-1)") (class "Default")
      (node (ref "ANT1") (pin "P$1") (pinfunction "1_P$1") (pintype "passive"))
      (node (ref "IC6") (pin "31") (pinfunction "RF_BG_31") (pintype "bidirectional"))
    )
    (net (code "101") (name "Net-(D1-DOUT)") (class "Default")
      (node (ref "D1") (pin "2") (pinfunction "DOUT_2") (pintype "output"))
      (node (ref "SV2") (pin "3") (pinfunction "3_3") (pintype "passive"))
    )
    (net (code "102") (name "Net-(D2-PadC)") (class "Default")
      (node (ref "D2") (pin "C") (pinfunction "C_C") (pintype "passive"))
      (node (ref "SJ1") (pin "1") (pinfunction "1_1") (pintype "passive"))
    )
    (net (code "103") (name "Net-(IC1-VCC)") (class "Default")
      (node (ref "C7") (pin "2") (pinfunction "2_2") (pintype "passive"))
      (node (ref "IC1") (pin "5") (pinfunction "VCC_5") (pintype "power_in"))
      (node (ref "J1") (pin "VBUS") (pinfunction "VBUS_VBUS") (pintype "bidirectional"))
      (node (ref "L2") (pin "1") (pinfunction "1_1") (pintype "passive"))
    )
    (net (code "104") (name "Net-(IC2-SW)") (class "Default")
      (node (ref "IC2") (pin "7") (pinfunction "SW_7") (pintype "output"))
      (node (ref "L1") (pin "1") (pinfunction "1_1") (pintype "passive"))
    )
    (net (code "105") (name "Net-(IC3G-VDD2)") (class "Default")
      (node (ref "C19") (pin "2") (pinfunction "2_2") (pintype "passive"))
      (node (ref "IC3") (pin "19") (pinfunction "VDD2_19") (pintype "bidirectional"))
      (node (ref "R8") (pin "1") (pinfunction "1_1") (pintype "passive"))
    )
    (net (code "106") (name "Net-(IC3G-VDDA)") (class "Default")
      (node (ref "C15") (pin "2") (pinfunction "2_2") (pintype "passive"))
      (node (ref "C16") (pin "2") (pinfunction "2_2") (pintype "passive"))
      (node (ref "IC3") (pin "21") (pinfunction "VREF+_21") (pintype "bidirectional"))
      (node (ref "IC3") (pin "22") (pinfunction "VDDA_22") (pintype "bidirectional"))
      (node (ref "L3") (pin "2") (pinfunction "2_2") (pintype "passive"))
    )
    (net (code "107") (name "Net-(IC3G-VSS)") (class "Default")
      (node (ref "C10") (pin "2") (pinfunction "2_2") (pintype "passive"))
      (node (ref "IC3") (pin "49") (pinfunction "VSS_49") (pintype "bidirectional"))
    )
    (net (code "108") (name "Net-(IC4-ISET)") (class "Default")
      (node (ref "IC4") (pin "2") (pinfunction "ISET_2") (pintype "input"))
      (node (ref "R9") (pin "1") (pinfunction "1_1") (pintype "passive"))
    )
    (net (code "109") (name "Net-(IC4-PRETERM)") (class "Default")
      (node (ref "IC4") (pin "4") (pinfunction "PRETERM_4") (pintype "input"))
      (node (ref "R6") (pin "1") (pinfunction "1_1") (pintype "passive"))
    )
    (net (code "110") (name "Net-(IC4-TS)") (class "Default")
      (node (ref "IC4") (pin "9") (pinfunction "TS_9") (pintype "input"))
      (node (ref "R13") (pin "1") (pinfunction "1_1") (pintype "passive"))
    )
    (net (code "111") (name "Net-(IC4-~{CHG})") (class "Default")
      (node (ref "IC4") (pin "8") (pinfunction "~{CHG}_8") (pintype "output"))
      (node (ref "R2") (pin "1") (pinfunction "1_1") (pintype "passive"))
    )
    (net (code "112") (name "Net-(IC6-SOP2)") (class "Default")
      (node (ref "IC6") (pin "23") (pinfunction "SOP2_23") (pintype "bidirectional"))
      (node (ref "R17") (pin "1") (pinfunction "1_1") (pintype "passive"))
    )
    (net (code "113") (name "Net-(IC6-TEST_58)") (class "Default")
      (node (ref "IC6") (pin "48") (pinfunction "TEST_58_48") (pintype "output"))
      (node (ref "TP14") (pin "TP") (pinfunction "TP_TP") (pintype "input"))
    )
    (net (code "114") (name "Net-(IC6-TEST_59)") (class "Default")
      (node (ref "IC6") (pin "49") (pinfunction "TEST_59_49") (pintype "output"))
      (node (ref "TP15") (pin "TP") (pinfunction "TP_TP") (pintype "input"))
    )
    (net (code "115") (name "Net-(IC6-TEST_60)") (class "Default")
      (node (ref "IC6") (pin "50") (pinfunction "TEST_60_50") (pintype "output"))
      (node (ref "TP16") (pin "TP") (pinfunction "TP_TP") (pintype "input"))
    )
    (net (code "116") (name "Net-(IC6-TEST_62)") (class "Default")
      (node (ref "IC6") (pin "52") (pinfunction "TEST_62_52") (pintype "output"))
      (node (ref "TP17") (pin "TP") (pinfunction "TP_TP") (pintype "input"))
    )
    (net (code "117") (name "Net-(IC6-~{UART_CTS})") (class "Default")
      (node (ref "IC6") (pin "51") (pinfunction "~{UART_CTS}_51") (pintype "bidirectional"))
      (node (ref "TP12") (pin "TP") (pinfunction "TP_TP") (pintype "input"))
    )
    (net (code "118") (name "Net-(IC6-~{UART_RTS})") (class "Default")
      (node (ref "IC6") (pin "44") (pinfunction "~{UART_RTS}_44") (pintype "bidirectional"))
      (node (ref "TP13") (pin "TP") (pinfunction "TP_TP") (pintype "input"))
    )
    (net (code "119") (name "Net-(J2-LEDK1)") (class "Default")
      (node (ref "J2") (pin "2") (pinfunction "LEDK1_2") (pintype "passive"))
      (node (ref "R47") (pin "2") (pinfunction "2_2") (pintype "passive"))
    )
    (net (code "120") (name "Net-(J2-LEDK2)") (class "Default")
      (node (ref "J2") (pin "3") (pinfunction "LEDK2_3") (pintype "passive"))
      (node (ref "R48") (pin "2") (pinfunction "2_2") (pintype "passive"))
    )
    (net (code "121") (name "Net-(J2-LEDK3)") (class "Default")
      (node (ref "J2") (pin "4") (pinfunction "LEDK3_4") (pintype "passive"))
      (node (ref "R49") (pin "2") (pinfunction "2_2") (pintype "passive"))
    )
    (net (code "122") (name "Net-(J2-LEDK4)") (class "Default")
      (node (ref "J2") (pin "5") (pinfunction "LEDK4_5") (pintype "passive"))
      (node (ref "R44") (pin "2") (pinfunction "2_2") (pintype "passive"))
    )
    (net (code "123") (name "Net-(LED1-PadA)") (class "Default")
      (node (ref "LED1") (pin "A") (pinfunction "A_A") (pintype "passive"))
      (node (ref "R1") (pin "1") (pinfunction "1_1") (pintype "passive"))
    )
    (net (code "124") (name "Net-(LED2-PadA)") (class "Default")
      (node (ref "LED2") (pin "A") (pinfunction "A_A") (pintype "passive"))
      (node (ref "R12") (pin "1") (pinfunction "1_1") (pintype "passive"))
    )
    (net (code "125") (name "Net-(LED3-PadA)") (class "Default")
      (node (ref "LED3") (pin "A") (pinfunction "A_A") (pintype "passive"))
      (node (ref "R14") (pin "1") (pinfunction "1_1") (pintype "passive"))
    )
    (net (code "126") (name "Net-(LED5-PadC)") (class "Default")
      (node (ref "LED5") (pin "C") (pinfunction "C_C") (pintype "passive"))
      (node (ref "R2") (pin "2") (pinfunction "2_2") (pintype "passive"))
    )
    (net (code "127") (name "Net-(Q1-B1)") (class "Default")
      (node (ref "Q1") (pin "1") (pinfunction "C1_1") (pintype "passive"))
      (node (ref "Q1") (pin "2") (pinfunction "B1_2") (pintype "passive"))
      (node (ref "Q1") (pin "3") (pinfunction "B2_3") (pintype "passive"))
      (node (ref "R16") (pin "1") (pinfunction "1_1") (pintype "passive"))
    )
    (net (code "128") (name "Net-(Q1-C2)") (class "Default")
      (node (ref "Q1") (pin "4") (pinfunction "C2_4") (pintype "passive"))
      (node (ref "Q2") (pin "4") (pinfunction "G_4") (pintype "bidirectional"))
      (node (ref "R15") (pin "1") (pinfunction "1_1") (pintype "passive"))
    )
    (net (code "129") (name "Net-(Q4A-D-Pad6)") (class "Default")
      (node (ref "Q4") (pin "3") (pinfunction "D_3") (pintype "bidirectional"))
      (node (ref "Q4") (pin "6") (pinfunction "D_6") (pintype "bidirectional"))
      (node (ref "Q4") (pin "EP1") (pinfunction "D_EP1") (pintype "bidirectional"))
      (node (ref "Q4") (pin "EP2") (pinfunction "D_EP2") (pintype "bidirectional"))
    )
    (net (code "130") (name "Net-(Q6-G)") (class "Default")
      (node (ref "Q6") (pin "4") (pinfunction "G_4") (pintype "bidirectional"))
      (node (ref "R45") (pin "2") (pinfunction "2_2") (pintype "passive"))
      (node (ref "S5") (pin "3") (pinfunction "S_3") (pintype "passive"))
    )
    (net (code "131") (name "Net-(Q8-D-Pad1)") (class "Default")
      (node (ref "Q8") (pin "1") (pinfunction "D_1") (pintype "bidirectional"))
      (node (ref "Q8") (pin "2") (pinfunction "D_2") (pintype "bidirectional"))
      (node (ref "Q8") (pin "5") (pinfunction "D_5") (pintype "bidirectional"))
      (node (ref "Q8") (pin "6") (pinfunction "D_6") (pintype "bidirectional"))
      (node (ref "Q8") (pin "EP1") (pinfunction "D_EP1") (pintype "bidirectional"))
      (node (ref "R44") (pin "1") (pinfunction "1_1") (pintype "passive"))
      (node (ref "R47") (pin "1") (pinfunction "1_1") (pintype "passive"))
      (node (ref "R48") (pin "1") (pinfunction "1_1") (pintype "passive"))
      (node (ref "R49") (pin "1") (pinfunction "1_1") (pintype "passive"))
    )
    (net (code "132") (name "Net-(SG1-1)") (class "Default")
      (node (ref "R26") (pin "1") (pinfunction "1_1") (pintype "passive"))
      (node (ref "SG1") (pin "P$1") (pinfunction "1_P$1") (pintype "passive"))
    )
    (net (code "133") (name "VABT_SWTICHED") (class "Default")
      (node (ref "D2") (pin "A") (pinfunction "A_A") (pintype "passive"))
      (node (ref "Q1") (pin "6") (pinfunction "E1_6") (pintype "passive"))
      (node (ref "Q2") (pin "1") (pinfunction "D_1") (pintype "bidirectional"))
      (node (ref "Q2") (pin "2") (pinfunction "D_2") (pintype "bidirectional"))
      (node (ref "Q2") (pin "3") (pinfunction "D_3") (pintype "bidirectional"))
      (node (ref "Q6") (pin "1") (pinfunction "D_1") (pintype "bidirectional"))
      (node (ref "Q6") (pin "2") (pinfunction "D_2") (pintype "bidirectional"))
      (node (ref "Q6") (pin "3") (pinfunction "D_3") (pintype "bidirectional"))
    )
    (net (code "134") (name "VBAT") (class "Default")
      (node (ref "C3") (pin "2") (pinfunction "2_2") (pintype "passive"))
      (node (ref "IC4") (pin "10") (pinfunction "OUT_10") (pintype "passive"))
      (node (ref "JP3") (pin "2") (pinfunction "2_2") (pintype "passive"))
      (node (ref "Q6") (pin "5") (pinfunction "S_5") (pintype "bidirectional"))
      (node (ref "Q6") (pin "6") (pinfunction "S_6") (pintype "bidirectional"))
      (node (ref "Q6") (pin "7") (pinfunction "S_7") (pintype "bidirectional"))
      (node (ref "Q6") (pin "8") (pinfunction "S_8") (pintype "bidirectional"))
      (node (ref "Q6") (pin "EP") (pinfunction "S_EP") (pintype "bidirectional"))
      (node (ref "R21") (pin "2") (pinfunction "2_2") (pintype "passive"))
      (node (ref "R45") (pin "1") (pinfunction "1_1") (pintype "passive"))
      (node (ref "R51") (pin "2") (pinfunction "2_2") (pintype "passive"))
    )
    (net (code "135") (name "VBUS") (class "Default")
      (node (ref "C1") (pin "2") (pinfunction "2_2") (pintype "passive"))
      (node (ref "C4") (pin "+") (pinfunction "+_+") (pintype "passive"))
      (node (ref "D3") (pin "A") (pinfunction "A_A") (pintype "passive"))
      (node (ref "IC4") (pin "1") (pinfunction "IN_1") (pintype "power_in"))
      (node (ref "L2") (pin "2") (pinfunction "2_2") (pintype "passive"))
      (node (ref "LED5") (pin "A") (pinfunction "A_A") (pintype "passive"))
      (node (ref "R10") (pin "2") (pinfunction "2_2") (pintype "passive"))
      (node (ref "SJ1") (pin "2") (pinfunction "2_2") (pintype "passive"))
    )
    (net (code "136") (name "unconnected-(IC2-FB-Pad4)") (class "Default")
      (node (ref "IC2") (pin "4") (pinfunction "FB_4") (pintype "input"))
    )
    (net (code "137") (name "unconnected-(IC2-PG-Pad6)") (class "Default")
      (node (ref "IC2") (pin "6") (pinfunction "PG_6") (pintype "bidirectional"))
    )
    (net (code "138") (name "unconnected-(IC4-~{PG}-Pad5)") (class "Default")
      (node (ref "IC4") (pin "5") (pinfunction "~{PG}_5") (pintype "output"))
    )
    (net (code "139") (name "unconnected-(IC6-ANT_SEL_1-Pad25)") (class "Default")
      (node (ref "IC6") (pin "25") (pinfunction "ANT_SEL_1_25") (pintype "output"))
    )
    (net (code "140") (name "unconnected-(IC6-ANT_SEL_2-Pad26)") (class "Default")
      (node (ref "IC6") (pin "26") (pinfunction "ANT_SEL_2_26") (pintype "output"))
    )
    (net (code "141") (name "unconnected-(IC6-SOP0-Pad34)") (class "Default")
      (node (ref "IC6") (pin "34") (pinfunction "SOP0_34") (pintype "bidirectional"))
    )
    (net (code "142") (name "unconnected-(IC6-SOP1-Pad24)") (class "Default")
      (node (ref "IC6") (pin "24") (pinfunction "SOP1_24") (pintype "bidirectional"))
    )
    (net (code "143") (name "unconnected-(IC9-INT-Pad7)") (class "Default")
      (node (ref "IC9") (pin "7") (pinfunction "INT_7") (pintype "output"))
    )
    (net (code "144") (name "unconnected-(J3-KEY-Pad7)") (class "Default")
      (node (ref "J3") (pin "7") (pinfunction "KEY_7") (pintype "bidirectional"))
    )
    (net (code "145") (name "unconnected-(J3-NC-Pad8)") (class "Default")
      (node (ref "J3") (pin "8") (pinfunction "NC_8") (pintype "no_connect"))
    )
    (net (code "146") (name "unconnected-(J3-SWO-Pad6)") (class "Default")
      (node (ref "J3") (pin "6") (pinfunction "SWO_6") (pintype "bidirectional"))
    )
    (net (code "147") (name "unconnected-(JP4-SWO-Pad6)") (class "Default")
      (node (ref "JP4") (pin "6") (pinfunction "SWO_6") (pintype "input"))
    )
    (net (code "148") (name "unconnected-(S5-O-Pad1)") (class "Default")
      (node (ref "S5") (pin "1") (pinfunction "O_1") (pintype "passive"))
    )
  )
)
